# EEZ_DIB_DCM220_r2B6.net
KiCad netlist of a schematic drawn in EAGLE
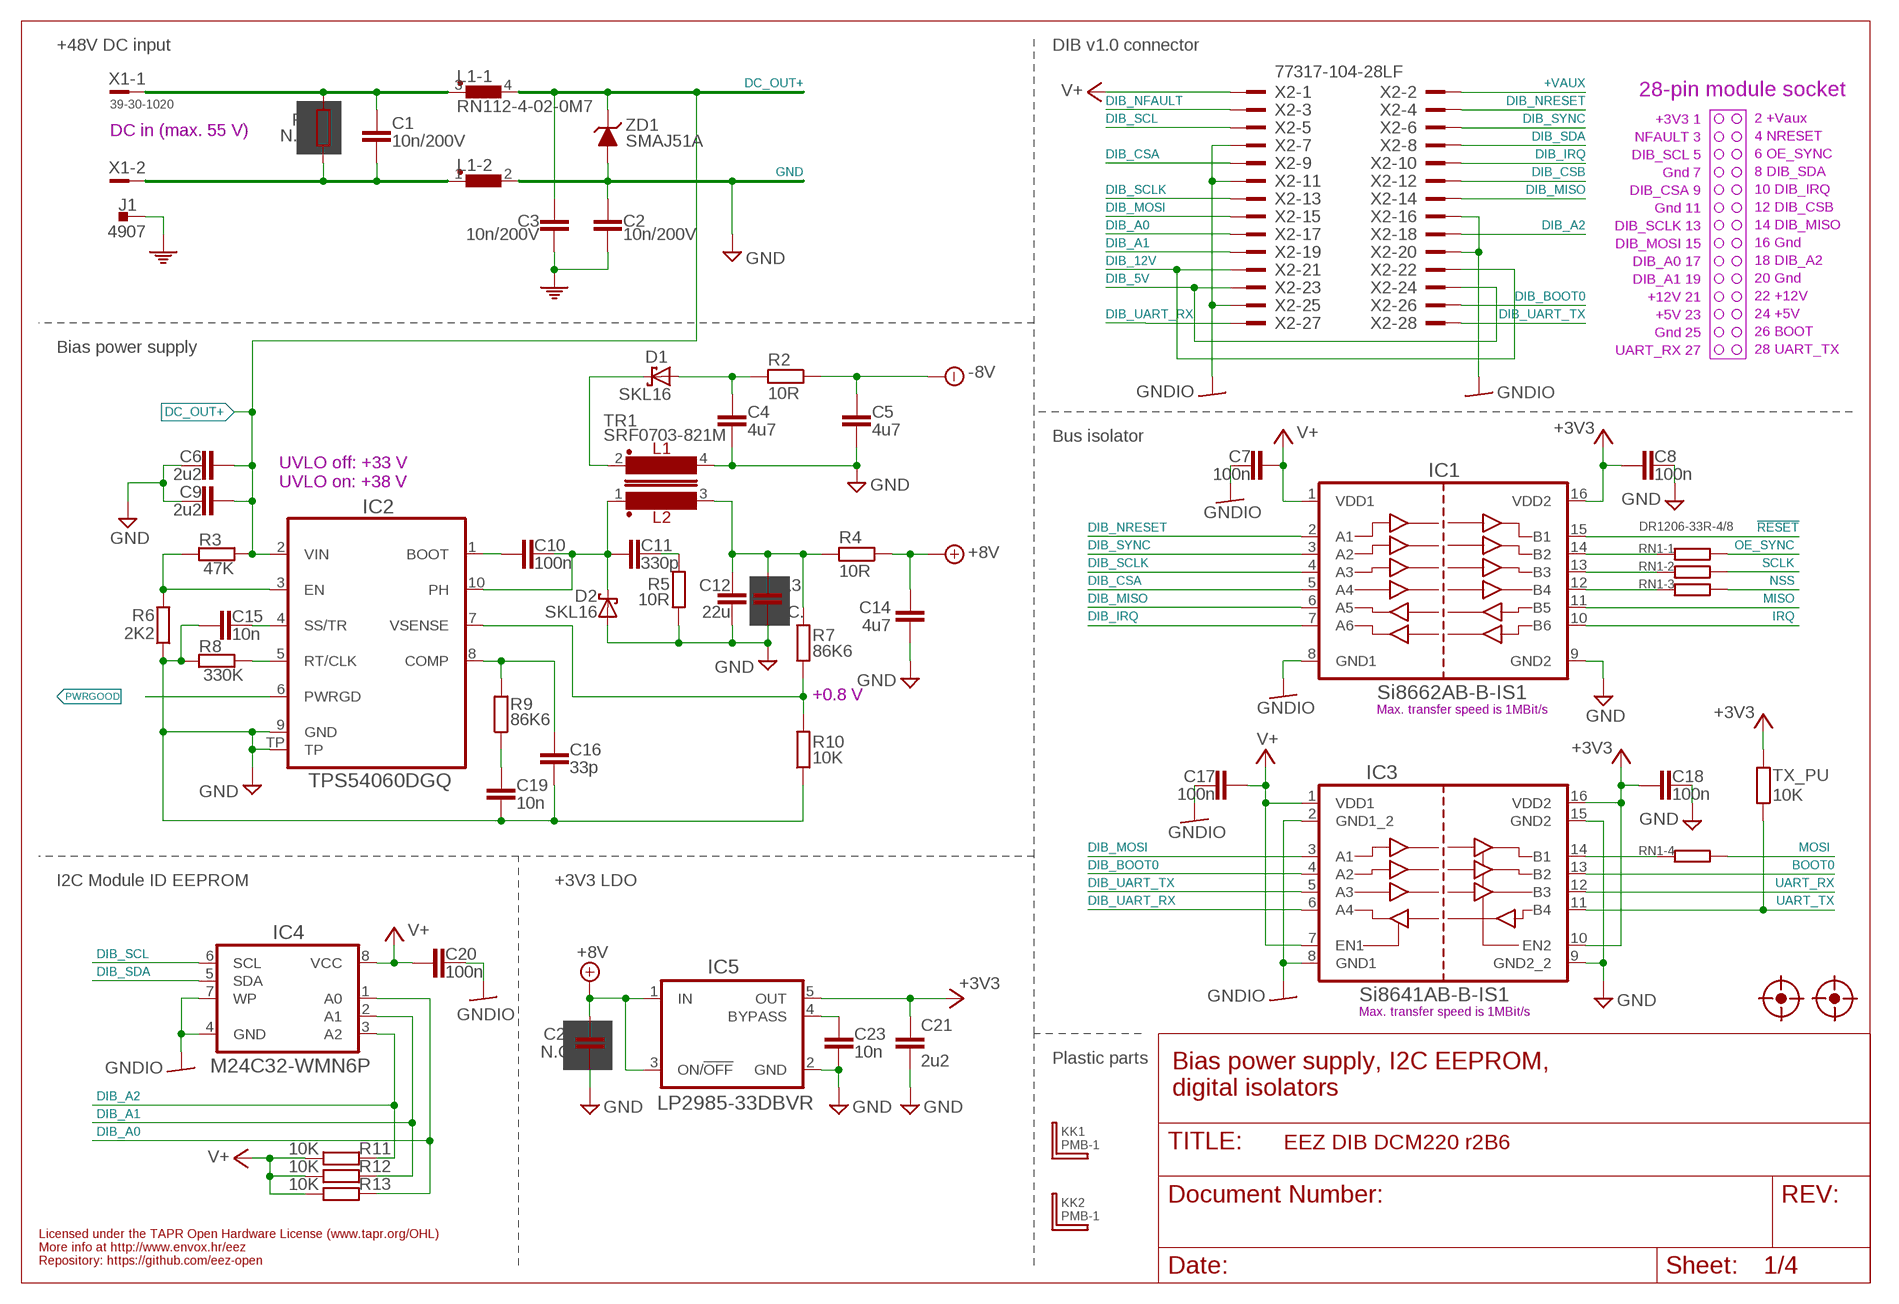
[diagram p0: schematic, sheet 1]
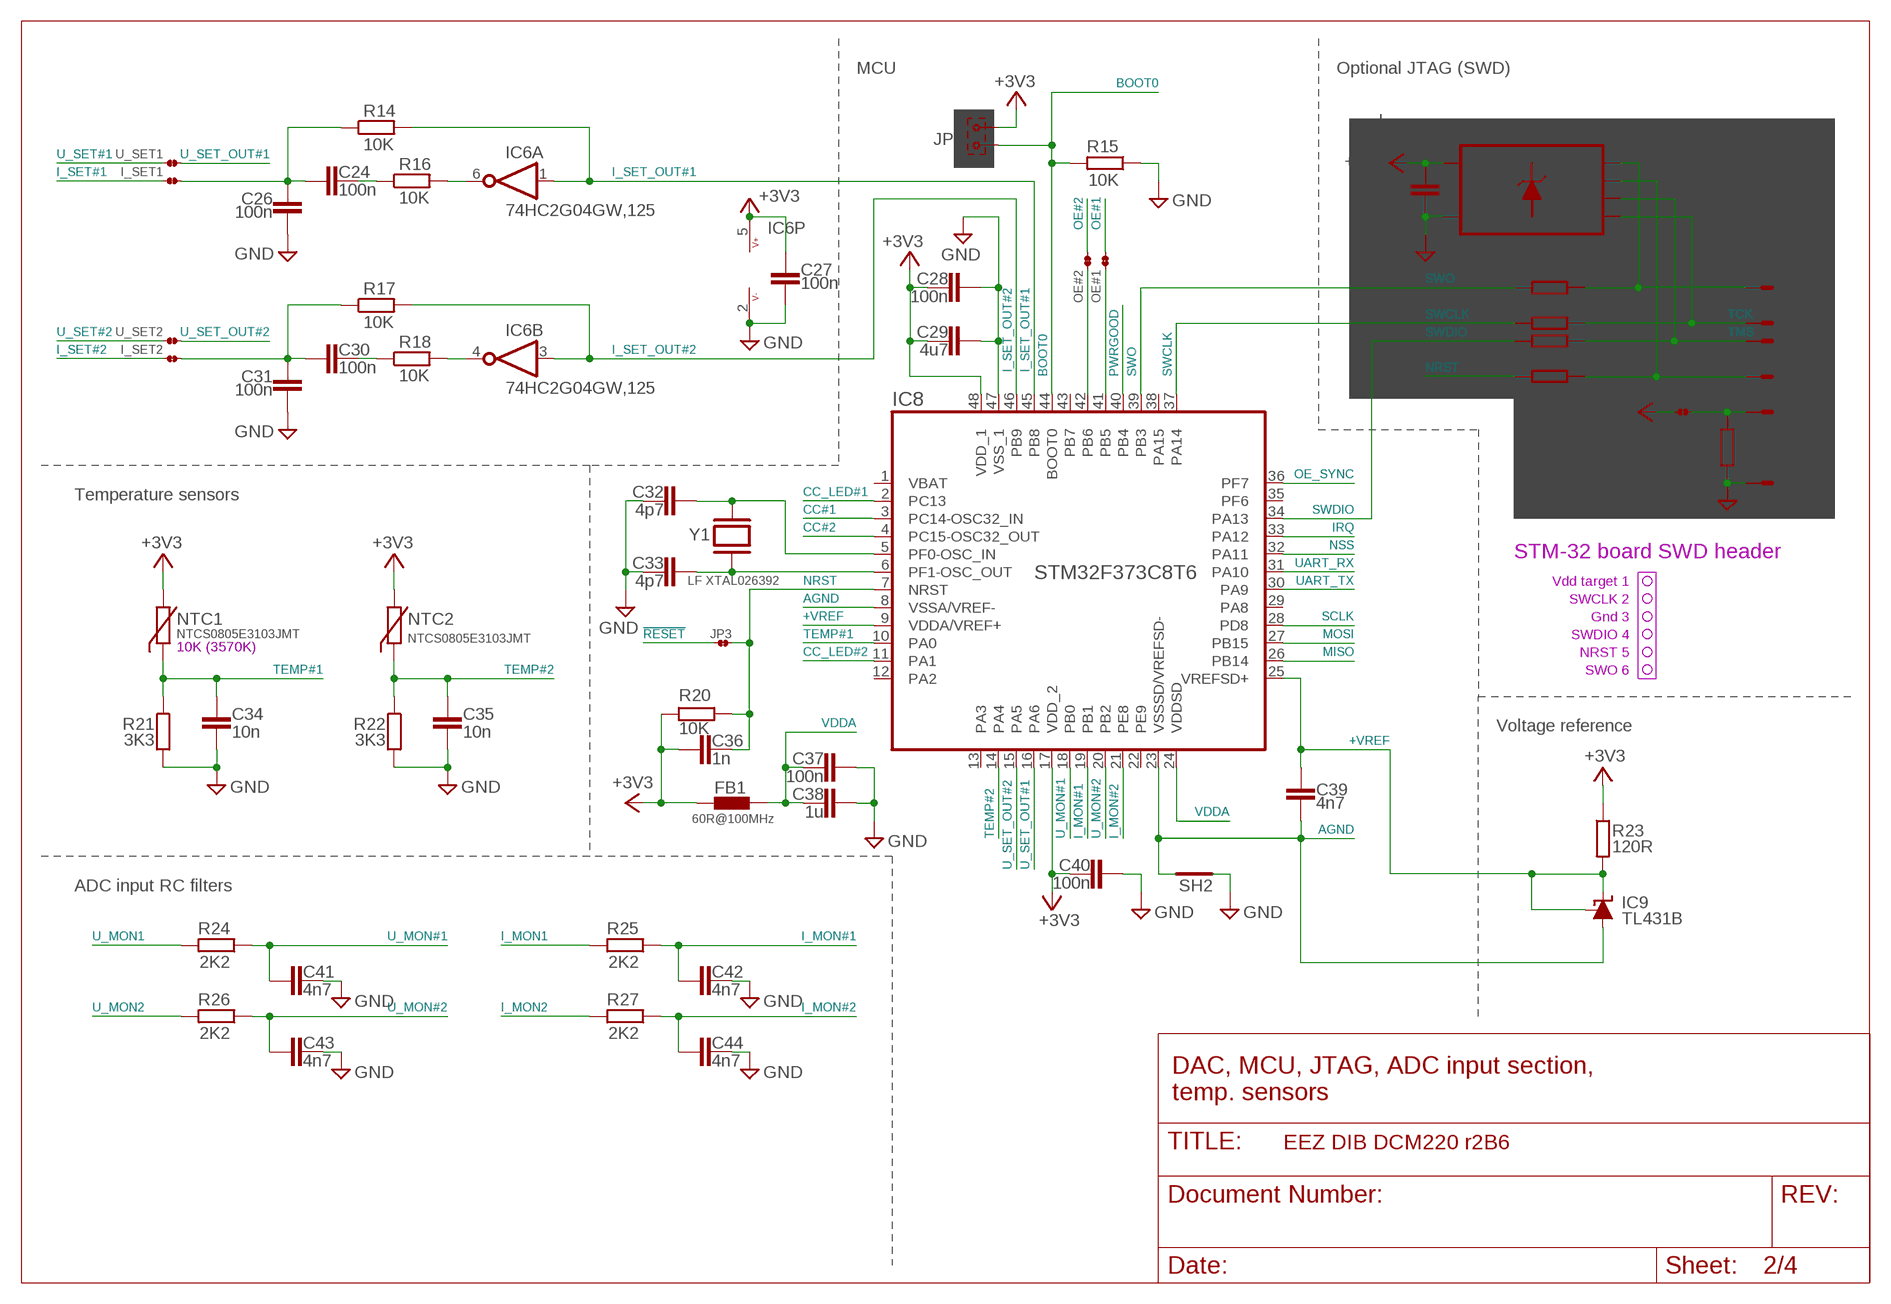
[diagram p1: schematic, sheet 2]
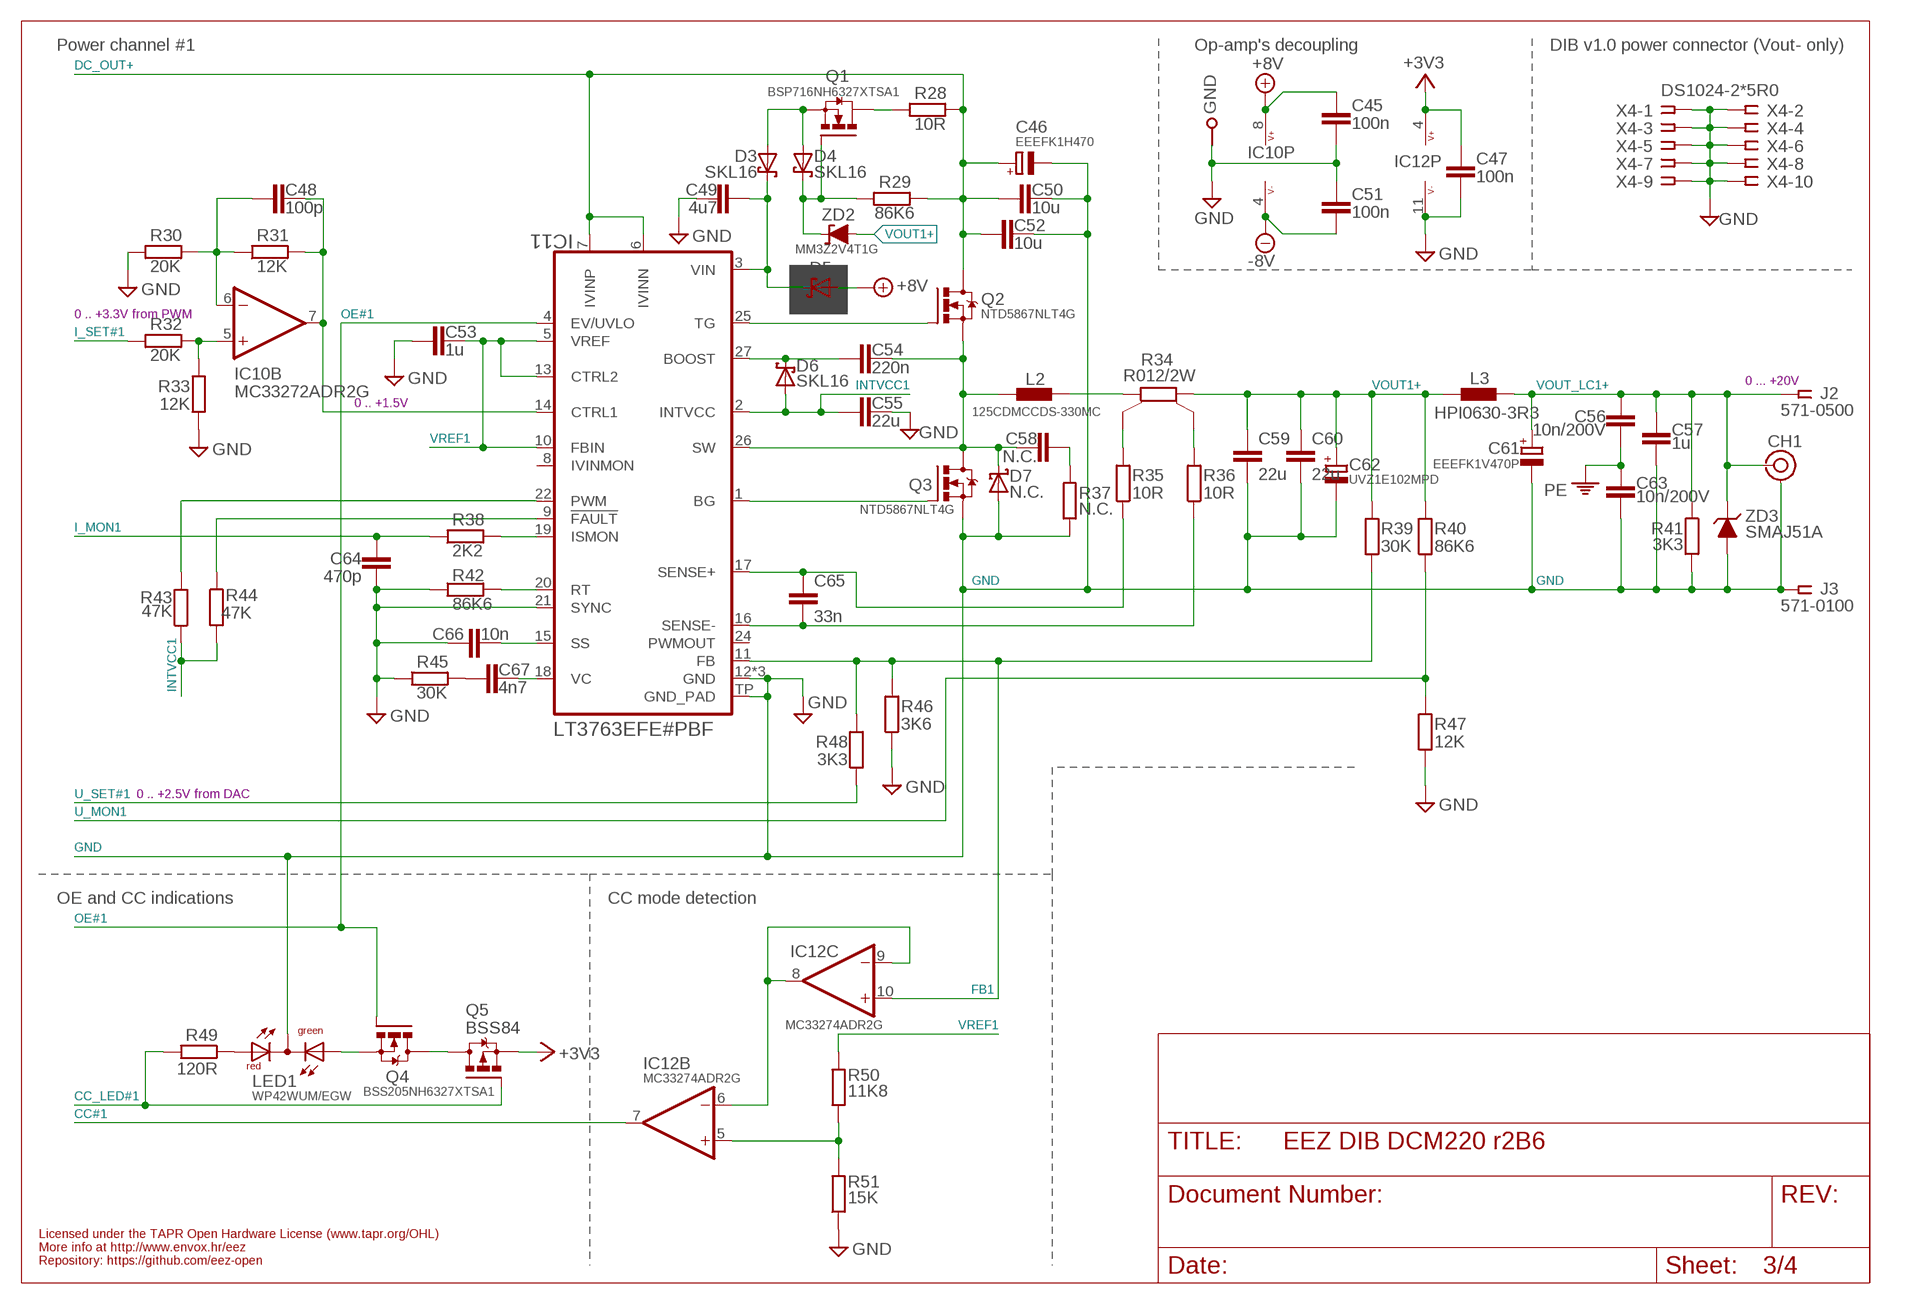
[diagram p2: schematic, sheet 3]
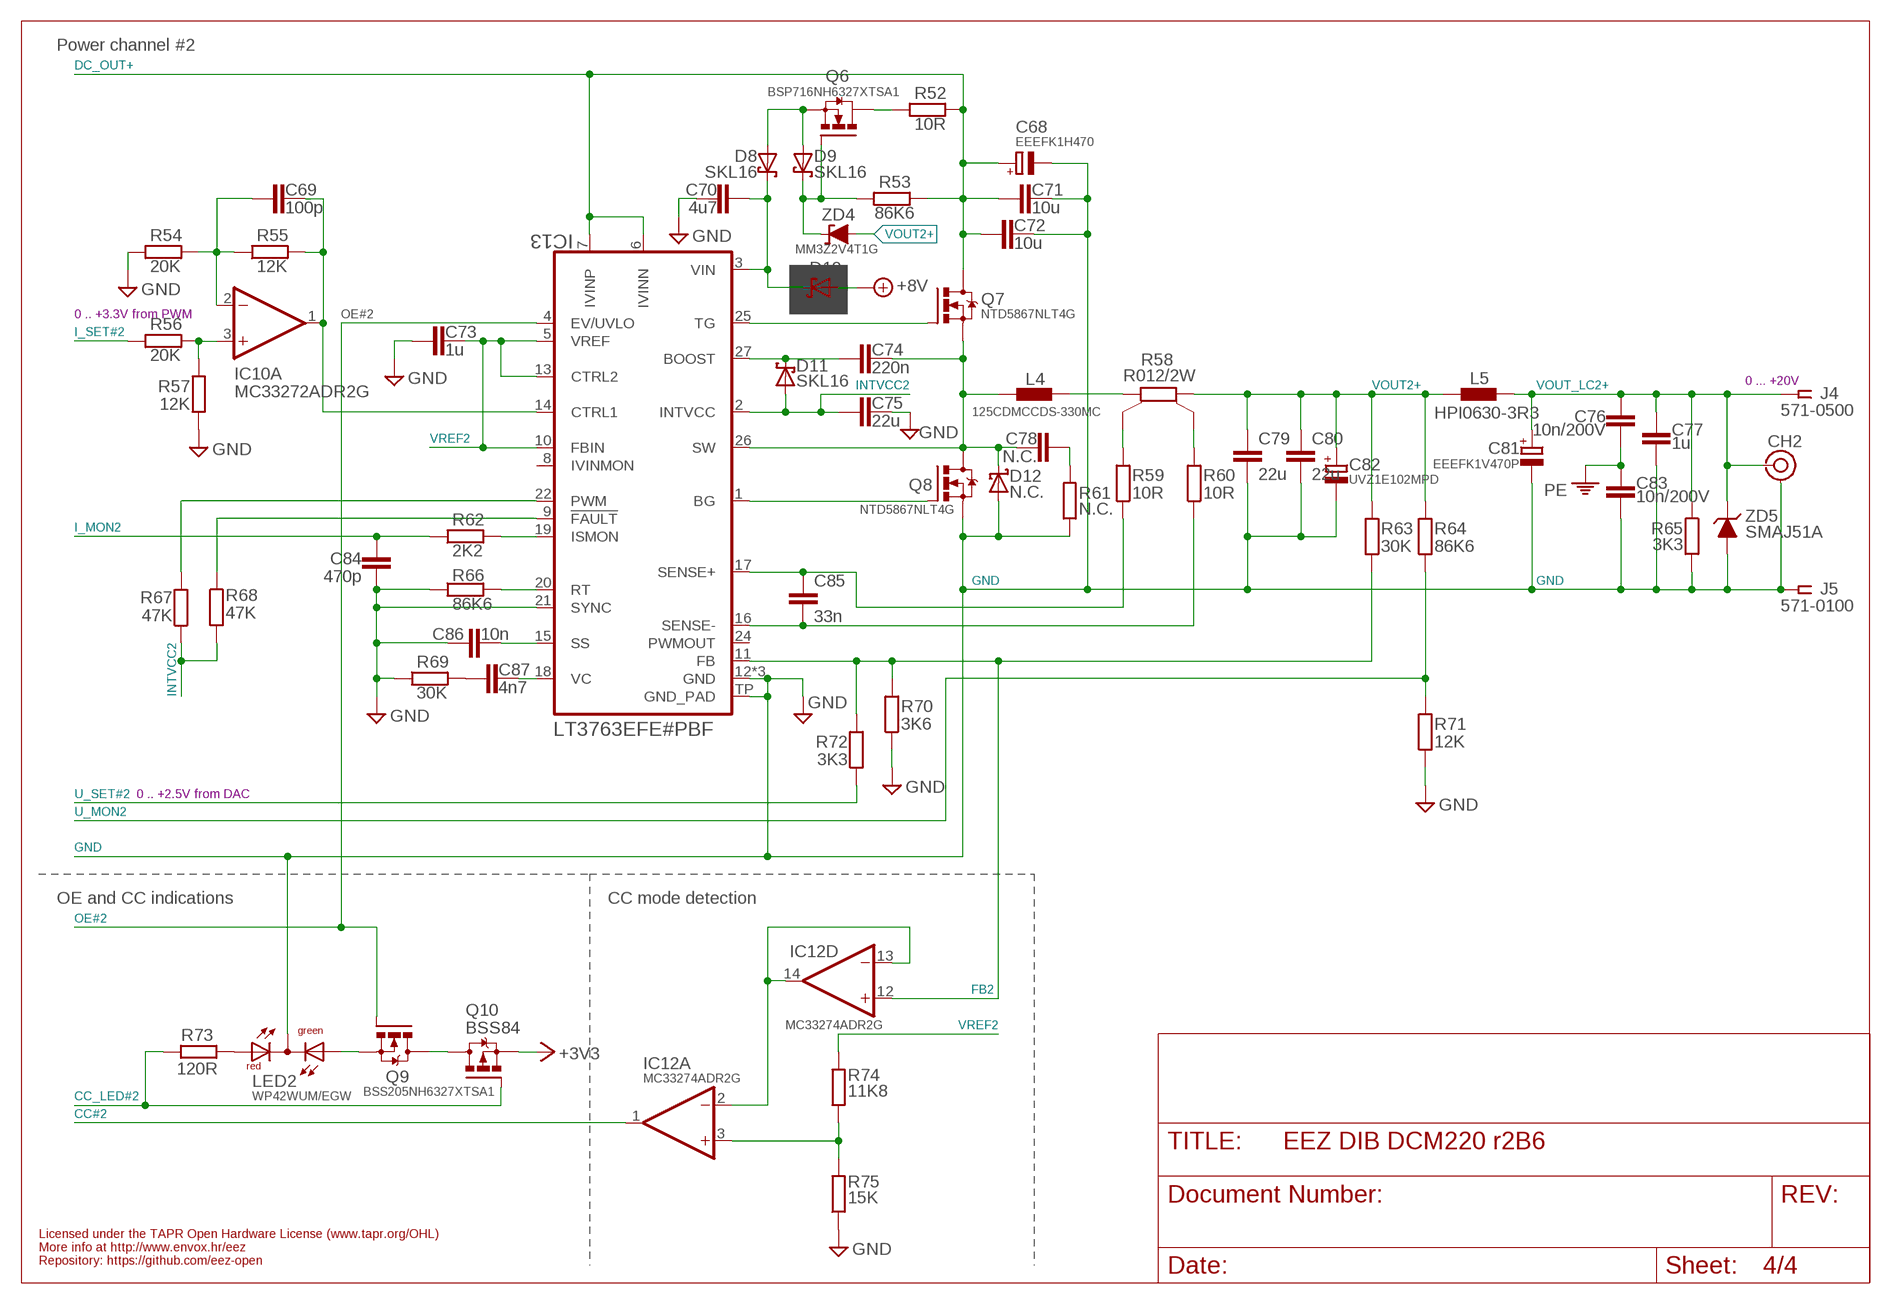
[diagram p3: schematic, sheet 4]

(export (version "E")
  (design (tool "Eeschema 10.0.6"))
  (components
    (comp (ref "C24")
      (value "100n")
      (footprint "eagle-import:C0603")
      (libsource (lib "eagle-import") (part "C-EUC0603"))
    )
    (comp (ref "C25")
      (value "N.C.")
      (footprint "eagle-import:C0603")
      (libsource (lib "eagle-import") (part "C-EUC0603"))
    )
    (comp (ref "C26")
      (value "100n")
      (footprint "eagle-import:C0603")
      (libsource (lib "eagle-import") (part "C-EUC0603"))
    )
    (comp (ref "C27")
      (value "100n")
      (footprint "eagle-import:C0603")
      (libsource (lib "eagle-import") (part "C-EUC0603"))
    )
    (comp (ref "C28")
      (value "100n")
      (footprint "eagle-import:C0603")
      (libsource (lib "eagle-import") (part "C-EUC0603"))
    )
    (comp (ref "C29")
      (value "4u7")
      (footprint "eagle-import:C1206")
      (libsource (lib "eagle-import") (part "C-EUC1206"))
    )
    (comp (ref "C30")
      (value "100n")
      (footprint "eagle-import:C0603")
      (libsource (lib "eagle-import") (part "C-EUC0603"))
    )
    (comp (ref "C31")
      (value "100n")
      (footprint "eagle-import:C0603")
      (libsource (lib "eagle-import") (part "C-EUC0603"))
    )
    (comp (ref "C32")
      (value "4p7")
      (footprint "eagle-import:C0603")
      (libsource (lib "eagle-import") (part "C-EUC0603"))
    )
    (comp (ref "C33")
      (value "4p7")
      (footprint "eagle-import:C0603")
      (libsource (lib "eagle-import") (part "C-EUC0603"))
    )
    (comp (ref "C34")
      (value "10n")
      (footprint "eagle-import:C0805")
      (libsource (lib "eagle-import") (part "C-EUC0805"))
    )
    (comp (ref "C35")
      (value "10n")
      (footprint "eagle-import:C0805")
      (libsource (lib "eagle-import") (part "C-EUC0805"))
    )
    (comp (ref "C36")
      (value "1n")
      (footprint "eagle-import:C0805")
      (libsource (lib "eagle-import") (part "C-EUC0805"))
    )
    (comp (ref "C37")
      (value "100n")
      (footprint "eagle-import:C0603")
      (libsource (lib "eagle-import") (part "C-EUC0603"))
    )
    (comp (ref "C38")
      (value "1u")
      (footprint "eagle-import:C0805")
      (libsource (lib "eagle-import") (part "C-EUC0805"))
    )
    (comp (ref "C39")
      (value "4n7")
      (footprint "eagle-import:C0805")
      (libsource (lib "eagle-import") (part "C-EUC0805"))
    )
    (comp (ref "C40")
      (value "100n")
      (footprint "eagle-import:C0603")
      (libsource (lib "eagle-import") (part "C-EUC0603"))
    )
    (comp (ref "C41")
      (value "4n7")
      (footprint "eagle-import:C0805")
      (libsource (lib "eagle-import") (part "C-EUC0805"))
    )
    (comp (ref "C42")
      (value "4n7")
      (footprint "eagle-import:C0805")
      (libsource (lib "eagle-import") (part "C-EUC0805"))
    )
    (comp (ref "C43")
      (value "4n7")
      (footprint "eagle-import:C0805")
      (libsource (lib "eagle-import") (part "C-EUC0805"))
    )
    (comp (ref "C44")
      (value "4n7")
      (footprint "eagle-import:C0805")
      (libsource (lib "eagle-import") (part "C-EUC0805"))
    )
    (comp (ref "FB1")
      (value "60R@100MHz")
      (footprint "eagle-import:BEAD0603")
      (libsource (lib "eagle-import") (part "FERRITE_BEAD0603"))
    )
    (comp (ref "IC6")
      (value "74HC2G04GW,125")
      (footprint "eagle-import:SOT65P210X110-6N")
      (libsource (lib "eagle-import") (part "74HC2G04"))
    )
    (comp (ref "IC7")
      (value "N.C.")
      (footprint "eagle-import:DRL6")
      (libsource (lib "eagle-import") (part "TPD4E001-DRL"))
    )
    (comp (ref "IC8")
      (value "STM32F373C8T6")
      (footprint "eagle-import:LQFP-48")
      (libsource (lib "eagle-import") (part "STM32F373C8T6"))
    )
    (comp (ref "IC9")
      (value "TL431B")
      (footprint "eagle-import:SOT103P240X110-3N")
      (libsource (lib "eagle-import") (part "TL431"))
    )
    (comp (ref "I_SET1")
      (value "JP2-NOCUT")
      (footprint "eagle-import:JP2-NOCUT")
      (libsource (lib "eagle-import") (part "JP2-NOCUT"))
    )
    (comp (ref "I_SET2")
      (value "JP2-NOCUT")
      (footprint "eagle-import:JP2-NOCUT")
      (libsource (lib "eagle-import") (part "JP2-NOCUT"))
    )
    (comp (ref "JP1")
      (value "JUMPER-2PIN-2MM")
      (footprint "eagle-import:2MM-2")
      (libsource (lib "eagle-import") (part "JUMPER-2PIN-2MM"))
    )
    (comp (ref "JP2")
      (value "JP2-CUT")
      (footprint "eagle-import:JP2-CUT")
      (libsource (lib "eagle-import") (part "JP2-CUT"))
    )
    (comp (ref "JP3")
      (value "JP2-NOCUT")
      (footprint "eagle-import:JP2-NOCUT")
      (libsource (lib "eagle-import") (part "JP2-NOCUT"))
    )
    (comp (ref "NTC1")
      (value "NTCS0805E3103JMT")
      (footprint "eagle-import:R_0805")
      (libsource (lib "eagle-import") (part "NTCR_0805"))
    )
    (comp (ref "NTC2")
      (value "NTCS0805E3103JMT")
      (footprint "eagle-import:R_0805")
      (libsource (lib "eagle-import") (part "NTCR_0805"))
    )
    (comp (ref "OE#1")
      (value "JP2-NOCUT")
      (footprint "eagle-import:JP2-NOCUT")
      (libsource (lib "eagle-import") (part "JP2-NOCUT"))
    )
    (comp (ref "OE#2")
      (value "JP2-NOCUT")
      (footprint "eagle-import:JP2-NOCUT")
      (libsource (lib "eagle-import") (part "JP2-NOCUT"))
    )
    (comp (ref "R14")
      (value "10K")
      (footprint "eagle-import:R0805")
      (libsource (lib "eagle-import") (part "R-EU_R0805"))
    )
    (comp (ref "R15")
      (value "10K")
      (footprint "eagle-import:R0805")
      (libsource (lib "eagle-import") (part "R-EU_R0805"))
    )
    (comp (ref "R16")
      (value "10K")
      (footprint "eagle-import:R0805")
      (libsource (lib "eagle-import") (part "R-EU_R0805"))
    )
    (comp (ref "R17")
      (value "10K")
      (footprint "eagle-import:R0805")
      (libsource (lib "eagle-import") (part "R-EU_R0805"))
    )
    (comp (ref "R18")
      (value "10K")
      (footprint "eagle-import:R0805")
      (libsource (lib "eagle-import") (part "R-EU_R0805"))
    )
    (comp (ref "R19")
      (value "N.C.")
      (footprint "eagle-import:R0805")
      (libsource (lib "eagle-import") (part "R-EU_R0805"))
    )
    (comp (ref "R20")
      (value "10K")
      (footprint "eagle-import:R0805")
      (libsource (lib "eagle-import") (part "R-EU_R0805"))
    )
    (comp (ref "R21")
      (value "3K3")
      (footprint "eagle-import:R0805")
      (libsource (lib "eagle-import") (part "R-EU_R0805"))
    )
    (comp (ref "R22")
      (value "3K3")
      (footprint "eagle-import:R0805")
      (libsource (lib "eagle-import") (part "R-EU_R0805"))
    )
    (comp (ref "R23")
      (value "120R")
      (footprint "eagle-import:R0805")
      (libsource (lib "eagle-import") (part "R-EU_R0805"))
    )
    (comp (ref "R24")
      (value "2K2")
      (footprint "eagle-import:R0805")
      (libsource (lib "eagle-import") (part "R-EU_R0805"))
    )
    (comp (ref "R25")
      (value "2K2")
      (footprint "eagle-import:R0805")
      (libsource (lib "eagle-import") (part "R-EU_R0805"))
    )
    (comp (ref "R26")
      (value "2K2")
      (footprint "eagle-import:R0805")
      (libsource (lib "eagle-import") (part "R-EU_R0805"))
    )
    (comp (ref "R27")
      (value "2K2")
      (footprint "eagle-import:R0805")
      (libsource (lib "eagle-import") (part "R-EU_R0805"))
    )
    (comp (ref "RN2")
      (value "N.C.")
      (footprint "eagle-import:CAY16")
      (libsource (lib "eagle-import") (part "R_ARRAY4"))
    )
    (comp (ref "SH2")
      (value "SHORTNOHOLE")
      (footprint "eagle-import:SHORT_NOHOLE")
      (libsource (lib "eagle-import") (part "SHORTNOHOLE"))
    )
    (comp (ref "U_SET1")
      (value "JP2-NOCUT")
      (footprint "eagle-import:JP2-NOCUT")
      (libsource (lib "eagle-import") (part "JP2-NOCUT"))
    )
    (comp (ref "U_SET2")
      (value "JP2-NOCUT")
      (footprint "eagle-import:JP2-NOCUT")
      (libsource (lib "eagle-import") (part "JP2-NOCUT"))
    )
    (comp (ref "X3")
      (value "N.C.")
      (footprint "eagle-import:22-23-2061")
      (fields (field (name "MF") "MOLEX") (field (name "MPN") "22-23-2061"))
      (libsource (lib "eagle-import") (part "22-23-2061"))
    )
    (comp (ref "Y1")
      (value "LF XTAL026392")
      (footprint "eagle-import:12SMX(B)")
      (libsource (lib "eagle-import") (part "XTAL7.5X5.1-B"))
    )
    (comp (ref "C45")
      (value "100n")
      (footprint "eagle-import:C0603")
      (libsource (lib "eagle-import") (part "C-EUC0603"))
    )
    (comp (ref "C46")
      (value "EEEFK1H470")
      (footprint "eagle-import:CAPAE830X1050N")
      (libsource (lib "eagle-import") (part "ECAPSMD8.3MM/HA0"))
    )
    (comp (ref "C47")
      (value "100n")
      (footprint "eagle-import:C0603")
      (libsource (lib "eagle-import") (part "C-EUC0603"))
    )
    (comp (ref "C48")
      (value "100p")
      (footprint "eagle-import:C0805")
      (libsource (lib "eagle-import") (part "C-EUC0805"))
    )
    (comp (ref "C49")
      (value "4u7")
      (footprint "eagle-import:C1206")
      (libsource (lib "eagle-import") (part "C-EUC1206"))
    )
    (comp (ref "C50")
      (value "10u")
      (footprint "eagle-import:C1210")
      (libsource (lib "eagle-import") (part "C-EUC1210"))
    )
    (comp (ref "C51")
      (value "100n")
      (footprint "eagle-import:C0603")
      (libsource (lib "eagle-import") (part "C-EUC0603"))
    )
    (comp (ref "C52")
      (value "10u")
      (footprint "eagle-import:C1210")
      (libsource (lib "eagle-import") (part "C-EUC1210"))
    )
    (comp (ref "C53")
      (value "1u")
      (footprint "eagle-import:C0805")
      (libsource (lib "eagle-import") (part "C-EUC0805"))
    )
    (comp (ref "C54")
      (value "220n")
      (footprint "eagle-import:C0805")
      (libsource (lib "eagle-import") (part "C-EUC0805"))
    )
    (comp (ref "C55")
      (value "22u")
      (footprint "eagle-import:C1206")
      (libsource (lib "eagle-import") (part "C-EUC1206"))
    )
    (comp (ref "C56")
      (value "10n/200V")
      (footprint "eagle-import:C1206")
      (libsource (lib "eagle-import") (part "C-EUC1206"))
    )
    (comp (ref "C57")
      (value "1u")
      (footprint "eagle-import:C0805")
      (libsource (lib "eagle-import") (part "C-EUC0805"))
    )
    (comp (ref "C58")
      (value "N.C.")
      (footprint "eagle-import:C0805")
      (libsource (lib "eagle-import") (part "C-EUC0805"))
    )
    (comp (ref "C59")
      (value "22u")
      (footprint "eagle-import:C1210")
      (libsource (lib "eagle-import") (part "C-EUC1210"))
    )
    (comp (ref "C60")
      (value "22u")
      (footprint "eagle-import:C1210")
      (libsource (lib "eagle-import") (part "C-EUC1210"))
    )
    (comp (ref "C61")
      (value "EEEFK1V470P")
      (footprint "eagle-import:CAPAE660X610N")
      (libsource (lib "eagle-import") (part "ECAPPANASONIC_H"))
    )
    (comp (ref "C62")
      (value "UVZ1E102MPD")
      (footprint "eagle-import:ECAP5_10.5")
      (libsource (lib "eagle-import") (part "ECAP5G_10.5MM"))
    )
    (comp (ref "C63")
      (value "10n/200V")
      (footprint "eagle-import:C1206")
      (libsource (lib "eagle-import") (part "C-EUC1206"))
    )
    (comp (ref "C64")
      (value "470p")
      (footprint "eagle-import:C0805")
      (libsource (lib "eagle-import") (part "C-EUC0805"))
    )
    (comp (ref "C65")
      (value "33n")
      (footprint "eagle-import:C0805")
      (libsource (lib "eagle-import") (part "C-EUC0805"))
    )
    (comp (ref "C66")
      (value "10n")
      (footprint "eagle-import:C0805")
      (libsource (lib "eagle-import") (part "C-EUC0805"))
    )
    (comp (ref "C67")
      (value "4n7")
      (footprint "eagle-import:C0805")
      (libsource (lib "eagle-import") (part "C-EUC0805"))
    )
    (comp (ref "CH1")
      (value "TEST_POINT-2")
      (footprint "eagle-import:TP_1.1MM_2")
      (libsource (lib "eagle-import") (part "TEST_POINT-2"))
    )
    (comp (ref "D3")
      (value "SKL16")
      (footprint "eagle-import:SOD123")
      (libsource (lib "eagle-import") (part "SCHOTTKYSOD123"))
    )
    (comp (ref "D4")
      (value "SKL16")
      (footprint "eagle-import:SOD123")
      (libsource (lib "eagle-import") (part "SCHOTTKYSOD123"))
    )
    (comp (ref "D5")
      (value "N.C.")
      (footprint "eagle-import:SOD123")
      (libsource (lib "eagle-import") (part "SCHOTTKYSOD123"))
    )
    (comp (ref "D6")
      (value "SKL16")
      (footprint "eagle-import:SOD123")
      (libsource (lib "eagle-import") (part "SCHOTTKYSOD123"))
    )
    (comp (ref "D7")
      (value "N.C.")
      (footprint "eagle-import:SMA")
      (libsource (lib "eagle-import") (part "SCHOTTKYSMA_DO-214AC"))
    )
    (comp (ref "GND")
      (value "TEST-PIN_0.9MM")
      (footprint "eagle-import:TEST-PIN_0.9MM")
      (libsource (lib "eagle-import") (part "TEST-PIN_0.9MM"))
    )
    (comp (ref "IC10")
      (value "MC33272ADR2G")
      (footprint "eagle-import:SOIC127P600X173-8N")
      (libsource (lib "eagle-import") (part "TL072SOIC8"))
    )
    (comp (ref "IC11")
      (value "LT3763EFE#PBF")
      (footprint "eagle-import:LTC_05-08-1663-EB")
      (libsource (lib "eagle-import") (part "LT3763EFE#PBF"))
    )
    (comp (ref "IC12")
      (value "MC33274ADR2G")
      (footprint "eagle-import:SOIC127P600X175-14N")
      (fields (field (name "MPN") "TL074ACD"))
      (libsource (lib "eagle-import") (part "TL074SOIC14"))
    )
    (comp (ref "J2")
      (value "571-0500")
      (footprint "eagle-import:DELTRON_571")
      (libsource (lib "eagle-import") (part "571-0500"))
    )
    (comp (ref "J3")
      (value "571-0100")
      (footprint "eagle-import:DELTRON_571")
      (libsource (lib "eagle-import") (part "571-0100"))
    )
    (comp (ref "L2")
      (value "125CDMCCDS-330MC")
      (footprint "eagle-import:125CDMCC_DS")
      (libsource (lib "eagle-import") (part "125CDMCC/DS"))
    )
    (comp (ref "L3")
      (value "HPI0630-3R3")
      (footprint "eagle-import:COILCRAFT_HPI0630")
      (libsource (lib "eagle-import") (part "COILCRAFT_HPI0630"))
    )
    (comp (ref "LED1")
      (value "WP42WUM/EGW")
      (footprint "eagle-import:L-42WUM-1EGWT")
      (libsource (lib "eagle-import") (part "LED_L-42WUM/1EGWT"))
    )
    (comp (ref "Q1")
      (value "BSP716NH6327XTSA1")
      (footprint "eagle-import:SOT223")
      (libsource (lib "eagle-import") (part "N-HEXFET-2D_?-SOT232IRLL014N"))
    )
    (comp (ref "Q2")
      (value "NTD5867NLT4G")
      (footprint "eagle-import:TO229P990X239-3N")
      (libsource (lib "eagle-import") (part "N-MOSFETDPAK"))
    )
    (comp (ref "Q3")
      (value "NTD5867NLT4G")
      (footprint "eagle-import:TO229P990X239-3N")
      (libsource (lib "eagle-import") (part "N-MOSFETDPAK"))
    )
    (comp (ref "Q4")
      (value "BSS205NH6327XTSA1")
      (footprint "eagle-import:SOT103P240X110-3N")
      (fields (field (name "MPN") "2N7002-7-F"))
      (libsource (lib "eagle-import") (part "2N7002"))
    )
    (comp (ref "Q5")
      (value "BSS84")
      (footprint "eagle-import:SOT95P237X112-3N")
      (fields (field (name "MPN") "IRLML2246TRPBF"))
      (libsource (lib "eagle-import") (part "IRLML2246TRPBF"))
    )
    (comp (ref "R28")
      (value "10R")
      (footprint "eagle-import:R0805")
      (libsource (lib "eagle-import") (part "R-EU_R0805"))
    )
    (comp (ref "R29")
      (value "86K6")
      (footprint "eagle-import:R0805")
      (libsource (lib "eagle-import") (part "R-EU_R0805"))
    )
    (comp (ref "R30")
      (value "20K")
      (footprint "eagle-import:R0805")
      (libsource (lib "eagle-import") (part "R-EU_R0805"))
    )
    (comp (ref "R31")
      (value "12K")
      (footprint "eagle-import:R0805")
      (libsource (lib "eagle-import") (part "R-EU_R0805"))
    )
    (comp (ref "R32")
      (value "20K")
      (footprint "eagle-import:R0805")
      (libsource (lib "eagle-import") (part "R-EU_R0805"))
    )
    (comp (ref "R33")
      (value "12K")
      (footprint "eagle-import:R0805")
      (libsource (lib "eagle-import") (part "R-EU_R0805"))
    )
    (comp (ref "R34")
      (value "R012/2W")
      (footprint "eagle-import:R_2512-4WIRE")
      (libsource (lib "eagle-import") (part "R-EU_4WIRE2512"))
    )
    (comp (ref "R35")
      (value "10R")
      (footprint "eagle-import:R0805")
      (libsource (lib "eagle-import") (part "R-EU_R0805"))
    )
    (comp (ref "R36")
      (value "10R")
      (footprint "eagle-import:R0805")
      (libsource (lib "eagle-import") (part "R-EU_R0805"))
    )
    (comp (ref "R37")
      (value "N.C.")
      (footprint "eagle-import:R1206")
      (libsource (lib "eagle-import") (part "R-EU_R1206"))
    )
    (comp (ref "R38")
      (value "2K2")
      (footprint "eagle-import:R0805")
      (libsource (lib "eagle-import") (part "R-EU_R0805"))
    )
    (comp (ref "R39")
      (value "30K")
      (footprint "eagle-import:R0805")
      (libsource (lib "eagle-import") (part "R-EU_R0805"))
    )
    (comp (ref "R40")
      (value "86K6")
      (footprint "eagle-import:R0805")
      (libsource (lib "eagle-import") (part "R-EU_R0805"))
    )
    (comp (ref "R41")
      (value "3K3")
      (footprint "eagle-import:R0805")
      (libsource (lib "eagle-import") (part "R-EU_R0805"))
    )
    (comp (ref "R42")
      (value "86K6")
      (footprint "eagle-import:R0805")
      (libsource (lib "eagle-import") (part "R-EU_R0805"))
    )
    (comp (ref "R43")
      (value "47K")
      (footprint "eagle-import:R0805")
      (libsource (lib "eagle-import") (part "R-EU_R0805"))
    )
    (comp (ref "R44")
      (value "47K")
      (footprint "eagle-import:R0805")
      (libsource (lib "eagle-import") (part "R-EU_R0805"))
    )
    (comp (ref "R45")
      (value "30K")
      (footprint "eagle-import:R0805")
      (libsource (lib "eagle-import") (part "R-EU_R0805"))
    )
    (comp (ref "R46")
      (value "3K6")
      (footprint "eagle-import:R0805")
      (libsource (lib "eagle-import") (part "R-EU_R0805"))
    )
    (comp (ref "R47")
      (value "12K")
      (footprint "eagle-import:R0805")
      (libsource (lib "eagle-import") (part "R-EU_R0805"))
    )
    (comp (ref "R48")
      (value "3K3")
      (footprint "eagle-import:R0805")
      (libsource (lib "eagle-import") (part "R-EU_R0805"))
    )
    (comp (ref "R49")
      (value "120R")
      (footprint "eagle-import:R0805")
      (libsource (lib "eagle-import") (part "R-EU_R0805"))
    )
    (comp (ref "R50")
      (value "11K8")
      (footprint "eagle-import:R0805")
      (libsource (lib "eagle-import") (part "R-EU_R0805"))
    )
    (comp (ref "R51")
      (value "15K")
      (footprint "eagle-import:R0805")
      (libsource (lib "eagle-import") (part "R-EU_R0805"))
    )
    (comp (ref "X4")
      (value "DS1024-2*5R0")
      (footprint "eagle-import:SSW-105-02-T-D-RA")
      (libsource (lib "eagle-import") (part "SSW-105-02-T-D-RA"))
    )
    (comp (ref "ZD2")
      (value "MM3Z2V4T1G")
      (footprint "eagle-import:SOD323-W")
      (libsource (lib "eagle-import") (part "ZENER-DIODESOD323"))
    )
    (comp (ref "ZD3")
      (value "SMAJ51A")
      (footprint "eagle-import:DO214AA")
      (libsource (lib "eagle-import") (part "P6SMB68A"))
    )
    (comp (ref "C68")
      (value "EEEFK1H470")
      (footprint "eagle-import:CAPAE830X1050N")
      (libsource (lib "eagle-import") (part "ECAPSMD8.3MM/HA0"))
    )
    (comp (ref "C69")
      (value "100p")
      (footprint "eagle-import:C0805")
      (libsource (lib "eagle-import") (part "C-EUC0805"))
    )
    (comp (ref "C70")
      (value "4u7")
      (footprint "eagle-import:C1206")
      (libsource (lib "eagle-import") (part "C-EUC1206"))
    )
    (comp (ref "C71")
      (value "10u")
      (footprint "eagle-import:C1210")
      (libsource (lib "eagle-import") (part "C-EUC1210"))
    )
    (comp (ref "C72")
      (value "10u")
      (footprint "eagle-import:C1210")
      (libsource (lib "eagle-import") (part "C-EUC1210"))
    )
    (comp (ref "C73")
      (value "1u")
      (footprint "eagle-import:C0805")
      (libsource (lib "eagle-import") (part "C-EUC0805"))
    )
    (comp (ref "C74")
      (value "220n")
      (footprint "eagle-import:C0805")
      (libsource (lib "eagle-import") (part "C-EUC0805"))
    )
    (comp (ref "C75")
      (value "22u")
      (footprint "eagle-import:C1206")
      (libsource (lib "eagle-import") (part "C-EUC1206"))
    )
    (comp (ref "C76")
      (value "10n/200V")
      (footprint "eagle-import:C1206")
      (libsource (lib "eagle-import") (part "C-EUC1206"))
    )
    (comp (ref "C77")
      (value "1u")
      (footprint "eagle-import:C0805")
      (libsource (lib "eagle-import") (part "C-EUC0805"))
    )
    (comp (ref "C78")
      (value "N.C.")
      (footprint "eagle-import:C0805")
      (libsource (lib "eagle-import") (part "C-EUC0805"))
    )
    (comp (ref "C79")
      (value "22u")
      (footprint "eagle-import:C1210")
      (libsource (lib "eagle-import") (part "C-EUC1210"))
    )
    (comp (ref "C80")
      (value "22u")
      (footprint "eagle-import:C1210")
      (libsource (lib "eagle-import") (part "C-EUC1210"))
    )
    (comp (ref "C81")
      (value "EEEFK1V470P")
      (footprint "eagle-import:CAPAE660X610N")
      (libsource (lib "eagle-import") (part "ECAPPANASONIC_H"))
    )
    (comp (ref "C82")
      (value "UVZ1E102MPD")
      (footprint "eagle-import:ECAP5_10.5")
      (libsource (lib "eagle-import") (part "ECAP5G_10.5MM"))
    )
    (comp (ref "C83")
      (value "10n/200V")
      (footprint "eagle-import:C1206")
      (libsource (lib "eagle-import") (part "C-EUC1206"))
    )
    (comp (ref "C84")
      (value "470p")
      (footprint "eagle-import:C0805")
      (libsource (lib "eagle-import") (part "C-EUC0805"))
    )
    (comp (ref "C85")
      (value "33n")
      (footprint "eagle-import:C0805")
      (libsource (lib "eagle-import") (part "C-EUC0805"))
    )
    (comp (ref "C86")
      (value "10n")
      (footprint "eagle-import:C0805")
      (libsource (lib "eagle-import") (part "C-EUC0805"))
    )
    (comp (ref "C87")
      (value "4n7")
      (footprint "eagle-import:C0805")
      (libsource (lib "eagle-import") (part "C-EUC0805"))
    )
    (comp (ref "CH2")
      (value "TEST_POINT-2")
      (footprint "eagle-import:TP_1.1MM_2")
      (libsource (lib "eagle-import") (part "TEST_POINT-2"))
    )
    (comp (ref "D8")
      (value "SKL16")
      (footprint "eagle-import:SOD123")
      (libsource (lib "eagle-import") (part "SCHOTTKYSOD123"))
    )
    (comp (ref "D9")
      (value "SKL16")
      (footprint "eagle-import:SOD123")
      (libsource (lib "eagle-import") (part "SCHOTTKYSOD123"))
    )
    (comp (ref "D10")
      (value "N.C.")
      (footprint "eagle-import:SOD123")
      (libsource (lib "eagle-import") (part "SCHOTTKYSOD123"))
    )
    (comp (ref "D11")
      (value "SKL16")
      (footprint "eagle-import:SOD123")
      (libsource (lib "eagle-import") (part "SCHOTTKYSOD123"))
    )
    (comp (ref "D12")
      (value "N.C.")
      (footprint "eagle-import:SMA")
      (libsource (lib "eagle-import") (part "SCHOTTKYSMA_DO-214AC"))
    )
    (comp (ref "IC13")
      (value "LT3763EFE#PBF")
      (footprint "eagle-import:LTC_05-08-1663-EB")
      (libsource (lib "eagle-import") (part "LT3763EFE#PBF"))
    )
    (comp (ref "J4")
      (value "571-0500")
      (footprint "eagle-import:DELTRON_571")
      (libsource (lib "eagle-import") (part "571-0500"))
    )
    (comp (ref "J5")
      (value "571-0100")
      (footprint "eagle-import:DELTRON_571")
      (libsource (lib "eagle-import") (part "571-0100"))
    )
    (comp (ref "L4")
      (value "125CDMCCDS-330MC")
      (footprint "eagle-import:125CDMCC_DS")
      (libsource (lib "eagle-import") (part "125CDMCC/DS"))
    )
    (comp (ref "L5")
      (value "HPI0630-3R3")
      (footprint "eagle-import:COILCRAFT_HPI0630")
      (libsource (lib "eagle-import") (part "COILCRAFT_HPI0630"))
    )
    (comp (ref "LED2")
      (value "WP42WUM/EGW")
      (footprint "eagle-import:L-42WUM-1EGWT")
      (libsource (lib "eagle-import") (part "LED_L-42WUM/1EGWT"))
    )
    (comp (ref "Q6")
      (value "BSP716NH6327XTSA1")
      (footprint "eagle-import:SOT223")
      (libsource (lib "eagle-import") (part "N-HEXFET-2D_?-SOT232IRLL014N"))
    )
    (comp (ref "Q7")
      (value "NTD5867NLT4G")
      (footprint "eagle-import:TO229P990X239-3N")
      (libsource (lib "eagle-import") (part "N-MOSFETDPAK"))
    )
    (comp (ref "Q8")
      (value "NTD5867NLT4G")
      (footprint "eagle-import:TO229P990X239-3N")
      (libsource (lib "eagle-import") (part "N-MOSFETDPAK"))
    )
    (comp (ref "Q9")
      (value "BSS205NH6327XTSA1")
      (footprint "eagle-import:SOT103P240X110-3N")
      (fields (field (name "MPN") "2N7002-7-F"))
      (libsource (lib "eagle-import") (part "2N7002"))
    )
    (comp (ref "Q10")
      (value "BSS84")
      (footprint "eagle-import:SOT95P237X112-3N")
      (fields (field (name "MPN") "IRLML2246TRPBF"))
      (libsource (lib "eagle-import") (part "IRLML2246TRPBF"))
    )
    (comp (ref "R52")
      (value "10R")
      (footprint "eagle-import:R0805")
      (libsource (lib "eagle-import") (part "R-EU_R0805"))
    )
    (comp (ref "R53")
      (value "86K6")
      (footprint "eagle-import:R0805")
      (libsource (lib "eagle-import") (part "R-EU_R0805"))
    )
    (comp (ref "R54")
      (value "20K")
      (footprint "eagle-import:R0805")
      (libsource (lib "eagle-import") (part "R-EU_R0805"))
    )
    (comp (ref "R55")
      (value "12K")
      (footprint "eagle-import:R0805")
      (libsource (lib "eagle-import") (part "R-EU_R0805"))
    )
    (comp (ref "R56")
      (value "20K")
      (footprint "eagle-import:R0805")
      (libsource (lib "eagle-import") (part "R-EU_R0805"))
    )
    (comp (ref "R57")
      (value "12K")
      (footprint "eagle-import:R0805")
      (libsource (lib "eagle-import") (part "R-EU_R0805"))
    )
    (comp (ref "R58")
      (value "R012/2W")
      (footprint "eagle-import:R_2512-4WIRE")
      (libsource (lib "eagle-import") (part "R-EU_4WIRE2512"))
    )
    (comp (ref "R59")
      (value "10R")
      (footprint "eagle-import:R0805")
      (libsource (lib "eagle-import") (part "R-EU_R0805"))
    )
    (comp (ref "R60")
      (value "10R")
      (footprint "eagle-import:R0805")
      (libsource (lib "eagle-import") (part "R-EU_R0805"))
    )
    (comp (ref "R61")
      (value "N.C.")
      (footprint "eagle-import:R1206")
      (libsource (lib "eagle-import") (part "R-EU_R1206"))
    )
    (comp (ref "R62")
      (value "2K2")
      (footprint "eagle-import:R0805")
      (libsource (lib "eagle-import") (part "R-EU_R0805"))
    )
    (comp (ref "R63")
      (value "30K")
      (footprint "eagle-import:R0805")
      (libsource (lib "eagle-import") (part "R-EU_R0805"))
    )
    (comp (ref "R64")
      (value "86K6")
      (footprint "eagle-import:R0805")
      (libsource (lib "eagle-import") (part "R-EU_R0805"))
    )
    (comp (ref "R65")
      (value "3K3")
      (footprint "eagle-import:R0805")
      (libsource (lib "eagle-import") (part "R-EU_R0805"))
    )
    (comp (ref "R66")
      (value "86K6")
      (footprint "eagle-import:R0805")
      (libsource (lib "eagle-import") (part "R-EU_R0805"))
    )
    (comp (ref "R67")
      (value "47K")
      (footprint "eagle-import:R0805")
      (libsource (lib "eagle-import") (part "R-EU_R0805"))
    )
    (comp (ref "R68")
      (value "47K")
      (footprint "eagle-import:R0805")
      (libsource (lib "eagle-import") (part "R-EU_R0805"))
    )
    (comp (ref "R69")
      (value "30K")
      (footprint "eagle-import:R0805")
      (libsource (lib "eagle-import") (part "R-EU_R0805"))
    )
    (comp (ref "R70")
      (value "3K6")
      (footprint "eagle-import:R0805")
      (libsource (lib "eagle-import") (part "R-EU_R0805"))
    )
    (comp (ref "R71")
      (value "12K")
      (footprint "eagle-import:R0805")
      (libsource (lib "eagle-import") (part "R-EU_R0805"))
    )
    (comp (ref "R72")
      (value "3K3")
      (footprint "eagle-import:R0805")
      (libsource (lib "eagle-import") (part "R-EU_R0805"))
    )
    (comp (ref "R73")
      (value "120R")
      (footprint "eagle-import:R0805")
      (libsource (lib "eagle-import") (part "R-EU_R0805"))
    )
    (comp (ref "R74")
      (value "11K8")
      (footprint "eagle-import:R0805")
      (libsource (lib "eagle-import") (part "R-EU_R0805"))
    )
    (comp (ref "R75")
      (value "15K")
      (footprint "eagle-import:R0805")
      (libsource (lib "eagle-import") (part "R-EU_R0805"))
    )
    (comp (ref "ZD4")
      (value "MM3Z2V4T1G")
      (footprint "eagle-import:SOD323-W")
      (libsource (lib "eagle-import") (part "ZENER-DIODESOD323"))
    )
    (comp (ref "ZD5")
      (value "SMAJ51A")
      (footprint "eagle-import:DO214AA")
      (libsource (lib "eagle-import") (part "P6SMB68A"))
    )
    (comp (ref "C1")
      (value "10n/200V")
      (footprint "eagle-import:C1206")
      (libsource (lib "eagle-import") (part "C-EUC1206"))
    )
    (comp (ref "C2")
      (value "10n/200V")
      (footprint "eagle-import:C1206")
      (libsource (lib "eagle-import") (part "C-EUC1206"))
    )
    (comp (ref "C3")
      (value "10n/200V")
      (footprint "eagle-import:C1206")
      (libsource (lib "eagle-import") (part "C-EUC1206"))
    )
    (comp (ref "C4")
      (value "4u7")
      (footprint "eagle-import:C1206")
      (libsource (lib "eagle-import") (part "C-EUC1206"))
    )
    (comp (ref "C5")
      (value "4u7")
      (footprint "eagle-import:C1206")
      (libsource (lib "eagle-import") (part "C-EUC1206"))
    )
    (comp (ref "C6")
      (value "2u2")
      (footprint "eagle-import:C1206")
      (libsource (lib "eagle-import") (part "C-EUC1206"))
    )
    (comp (ref "C7")
      (value "100n")
      (footprint "eagle-import:C0603")
      (libsource (lib "eagle-import") (part "C-EUC0603"))
    )
    (comp (ref "C8")
      (value "100n")
      (footprint "eagle-import:C0603")
      (libsource (lib "eagle-import") (part "C-EUC0603"))
    )
    (comp (ref "C9")
      (value "2u2")
      (footprint "eagle-import:C1206")
      (libsource (lib "eagle-import") (part "C-EUC1206"))
    )
    (comp (ref "C10")
      (value "100n")
      (footprint "eagle-import:C0603")
      (libsource (lib "eagle-import") (part "C-EUC0603"))
    )
    (comp (ref "C11")
      (value "330p")
      (footprint "eagle-import:C0805")
      (libsource (lib "eagle-import") (part "C-EUC0805"))
    )
    (comp (ref "C12")
      (value "22u")
      (footprint "eagle-import:C1206")
      (libsource (lib "eagle-import") (part "C-EUC1206"))
    )
    (comp (ref "C13")
      (value "N.C.")
      (footprint "eagle-import:C1206")
      (libsource (lib "eagle-import") (part "C-EUC1206"))
    )
    (comp (ref "C14")
      (value "4u7")
      (footprint "eagle-import:C1206")
      (libsource (lib "eagle-import") (part "C-EUC1206"))
    )
    (comp (ref "C15")
      (value "10n")
      (footprint "eagle-import:C0805")
      (libsource (lib "eagle-import") (part "C-EUC0805"))
    )
    (comp (ref "C16")
      (value "33p")
      (footprint "eagle-import:C0603")
      (libsource (lib "eagle-import") (part "C-EUC0603"))
    )
    (comp (ref "C17")
      (value "100n")
      (footprint "eagle-import:C0603")
      (libsource (lib "eagle-import") (part "C-EUC0603"))
    )
    (comp (ref "C18")
      (value "100n")
      (footprint "eagle-import:C0603")
      (libsource (lib "eagle-import") (part "C-EUC0603"))
    )
    (comp (ref "C19")
      (value "10n")
      (footprint "eagle-import:C0805")
      (libsource (lib "eagle-import") (part "C-EUC0805"))
    )
    (comp (ref "C20")
      (value "100n")
      (footprint "eagle-import:C0603")
      (libsource (lib "eagle-import") (part "C-EUC0603"))
    )
    (comp (ref "C21")
      (value "2u2")
      (footprint "eagle-import:C1206")
      (libsource (lib "eagle-import") (part "C-EUC1206"))
    )
    (comp (ref "C22")
      (value "N.C.")
      (footprint "eagle-import:C0805")
      (libsource (lib "eagle-import") (part "C-EUC0805"))
    )
    (comp (ref "C23")
      (value "10n")
      (footprint "eagle-import:C0805")
      (libsource (lib "eagle-import") (part "C-EUC0805"))
    )
    (comp (ref "D1")
      (value "SKL16")
      (footprint "eagle-import:SOD123")
      (libsource (lib "eagle-import") (part "SCHOTTKYSOD123"))
    )
    (comp (ref "D2")
      (value "SKL16")
      (footprint "eagle-import:SOD123")
      (libsource (lib "eagle-import") (part "SCHOTTKYSOD123"))
    )
    (comp (ref "FM1")
      (value "FIDUCIAL_2")
      (footprint "eagle-import:FIDUCIAL_DUAL")
      (libsource (lib "eagle-import") (part "FIDUCIAL_2"))
    )
    (comp (ref "FM2")
      (value "FIDUCIAL_2")
      (footprint "eagle-import:FIDUCIAL_DUAL")
      (libsource (lib "eagle-import") (part "FIDUCIAL_2"))
    )
    (comp (ref "IC1")
      (value "Si8662AB-B-IS1")
      (footprint "eagle-import:SOIC-16")
      (libsource (lib "eagle-import") (part "SI8662NSOIC-16"))
    )
    (comp (ref "IC2")
      (value "TPS54060DGQ")
      (footprint "eagle-import:SOP50P490X110-11N")
      (fields (field (name "MPN") "TPS54060ADGQ"))
      (libsource (lib "eagle-import") (part "TPS54060DGQ"))
    )
    (comp (ref "IC3")
      (value "Si8641AB-B-IS1")
      (footprint "eagle-import:SOIC-16")
      (libsource (lib "eagle-import") (part "SI8641NSOIC-16"))
    )
    (comp (ref "IC4")
      (value "M24C32-WMN6P")
      (footprint "eagle-import:SOIC127P600X173-8N")
      (libsource (lib "eagle-import") (part "AT24CXXSOIC8"))
    )
    (comp (ref "IC5")
      (value "LP2985-33DBVR")
      (footprint "eagle-import:SOT95P270X145-5N")
      (libsource (lib "eagle-import") (part "LP2985"))
    )
    (comp (ref "J1")
      (value "4907")
      (footprint "eagle-import:PCB_TAB-4907")
      (libsource (lib "eagle-import") (part "PCB_TAB-4907"))
    )
    (comp (ref "KK1")
      (value "PMB-1")
      (footprint "eagle-import:PCB-MB")
      (libsource (lib "eagle-import") (part "PCB-MB"))
    )
    (comp (ref "KK2")
      (value "PMB-1")
      (footprint "eagle-import:PCB-MB")
      (libsource (lib "eagle-import") (part "PCB-MB"))
    )
    (comp (ref "L1")
      (value "RN112-4-02-0M7")
      (footprint "eagle-import:RN112")
      (libsource (lib "eagle-import") (part "RN112"))
    )
    (comp (ref "R1")
      (value "N.C.")
      (footprint "eagle-import:R2512")
      (libsource (lib "eagle-import") (part "R-EU_R2512"))
    )
    (comp (ref "R2")
      (value "10R")
      (footprint "eagle-import:R0805")
      (libsource (lib "eagle-import") (part "R-EU_R0805"))
    )
    (comp (ref "R3")
      (value "47K")
      (footprint "eagle-import:R0805")
      (libsource (lib "eagle-import") (part "R-EU_R0805"))
    )
    (comp (ref "R4")
      (value "10R")
      (footprint "eagle-import:R0805")
      (libsource (lib "eagle-import") (part "R-EU_R0805"))
    )
    (comp (ref "R5")
      (value "10R")
      (footprint "eagle-import:R0805")
      (libsource (lib "eagle-import") (part "R-EU_R0805"))
    )
    (comp (ref "R6")
      (value "2K2")
      (footprint "eagle-import:R0805")
      (libsource (lib "eagle-import") (part "R-EU_R0805"))
    )
    (comp (ref "R7")
      (value "86K6")
      (footprint "eagle-import:R0805")
      (libsource (lib "eagle-import") (part "R-EU_R0805"))
    )
    (comp (ref "R8")
      (value "330K")
      (footprint "eagle-import:R0805")
      (libsource (lib "eagle-import") (part "R-EU_R0805"))
    )
    (comp (ref "R9")
      (value "86K6")
      (footprint "eagle-import:R0805")
      (libsource (lib "eagle-import") (part "R-EU_R0805"))
    )
    (comp (ref "R10")
      (value "10K")
      (footprint "eagle-import:R0805")
      (libsource (lib "eagle-import") (part "R-EU_R0805"))
    )
    (comp (ref "R11")
      (value "10K")
      (footprint "eagle-import:R0805")
      (libsource (lib "eagle-import") (part "R-EU_R0805"))
    )
    (comp (ref "R12")
      (value "10K")
      (footprint "eagle-import:R0805")
      (libsource (lib "eagle-import") (part "R-EU_R0805"))
    )
    (comp (ref "R13")
      (value "10K")
      (footprint "eagle-import:R0805")
      (libsource (lib "eagle-import") (part "R-EU_R0805"))
    )
    (comp (ref "RN1")
      (value "DR1206-33R-4/8")
      (footprint "eagle-import:CAY16")
      (libsource (lib "eagle-import") (part "R_ARRAY4"))
    )
    (comp (ref "TR1")
      (value "SRF0703-821M")
      (footprint "eagle-import:SRF0703")
      (libsource (lib "eagle-import") (part "BOURNS_SRF0703INV"))
    )
    (comp (ref "TX_PU")
      (value "10K")
      (footprint "eagle-import:R0805")
      (libsource (lib "eagle-import") (part "R-EU_R0805"))
    )
    (comp (ref "X1")
      (value "39-30-1020")
      (footprint "eagle-import:MINIFIT_39301020")
      (libsource (lib "eagle-import") (part "MINIFIT_39301020"))
    )
    (comp (ref "X2")
      (value "77317-104-28LF")
      (footprint "eagle-import:77317-104-28LF")
      (libsource (lib "eagle-import") (part "77317-104-28LF"))
    )
    (comp (ref "ZD1")
      (value "SMAJ51A")
      (footprint "eagle-import:DO214AA")
      (libsource (lib "eagle-import") (part "P6SMB68A"))
    )
  )
  (nets
    (net (code "1") (name "+3V3") (class "Default")
      (node (ref "C18") (pin "2") (pinfunction "2_2") (pintype "passive"))
      (node (ref "C21") (pin "1") (pinfunction "1_1") (pintype "passive"))
      (node (ref "C25") (pin "1") (pinfunction "1_1") (pintype "passive"))
      (node (ref "C27") (pin "1") (pinfunction "1_1") (pintype "passive"))
      (node (ref "C28") (pin "2") (pinfunction "2_2") (pintype "passive"))
      (node (ref "C29") (pin "1") (pinfunction "1_1") (pintype "passive"))
      (node (ref "C36") (pin "2") (pinfunction "2_2") (pintype "passive"))
      (node (ref "C40") (pin "2") (pinfunction "2_2") (pintype "passive"))
      (node (ref "C47") (pin "1") (pinfunction "1_1") (pintype "passive"))
      (node (ref "C8") (pin "2") (pinfunction "2_2") (pintype "passive"))
      (node (ref "FB1") (pin "P$1") (pinfunction "1_P$1") (pintype "passive"))
      (node (ref "IC1") (pin "16") (pinfunction "VDD2_16") (pintype "passive"))
      (node (ref "IC12") (pin "4") (pinfunction "V+_4") (pintype "power_in"))
      (node (ref "IC3") (pin "10") (pinfunction "EN2_10") (pintype "input"))
      (node (ref "IC3") (pin "16") (pinfunction "VDD2_16") (pintype "passive"))
      (node (ref "IC5") (pin "5") (pinfunction "OUT_5") (pintype "passive"))
      (node (ref "IC6") (pin "5") (pinfunction "V+_5") (pintype "power_in"))
      (node (ref "IC7") (pin "6") (pinfunction "VCC_6") (pintype "passive"))
      (node (ref "IC8") (pin "17") (pinfunction "VDD_2_17") (pintype "passive"))
      (node (ref "IC8") (pin "48") (pinfunction "VDD_1_48") (pintype "bidirectional"))
      (node (ref "JP1") (pin "1") (pinfunction "1_1") (pintype "passive"))
      (node (ref "JP2") (pin "1") (pinfunction "1_1") (pintype "passive"))
      (node (ref "NTC1") (pin "1") (pinfunction "P$1_1") (pintype "bidirectional"))
      (node (ref "NTC2") (pin "1") (pinfunction "P$1_1") (pintype "bidirectional"))
      (node (ref "Q10") (pin "2") (pinfunction "S_2") (pintype "passive"))
      (node (ref "Q5") (pin "2") (pinfunction "S_2") (pintype "passive"))
      (node (ref "R20") (pin "1") (pinfunction "1_1") (pintype "passive"))
      (node (ref "R23") (pin "1") (pinfunction "1_1") (pintype "passive"))
      (node (ref "TX_PU") (pin "2") (pinfunction "2_2") (pintype "passive"))
    )
    (net (code "2") (name "+8V") (class "Default")
      (node (ref "C14") (pin "1") (pinfunction "1_1") (pintype "passive"))
      (node (ref "C22") (pin "2") (pinfunction "2_2") (pintype "passive"))
      (node (ref "C45") (pin "1") (pinfunction "1_1") (pintype "passive"))
      (node (ref "D10") (pin "A") (pinfunction "A_A") (pintype "passive"))
      (node (ref "D5") (pin "A") (pinfunction "A_A") (pintype "passive"))
      (node (ref "IC10") (pin "8") (pinfunction "V+_8") (pintype "power_in"))
      (node (ref "IC5") (pin "1") (pinfunction "IN_1") (pintype "input"))
      (node (ref "IC5") (pin "3") (pinfunction "ON/~{OFF}_3") (pintype "input"))
      (node (ref "R4") (pin "1") (pinfunction "1_1") (pintype "passive"))
    )
    (net (code "3") (name "+VAUX") (class "Default")
      (node (ref "X2") (pin "2") (pinfunction "1_2") (pintype "passive"))
    )
    (net (code "4") (name "+VREF") (class "Default")
      (node (ref "C39") (pin "2") (pinfunction "2_2") (pintype "passive"))
      (node (ref "IC8") (pin "25") (pinfunction "VREFSD+_25") (pintype "passive"))
      (node (ref "IC8") (pin "9") (pinfunction "VDDA/VREF+_9") (pintype "passive"))
      (node (ref "IC9") (pin "1") (pinfunction "C_1") (pintype "passive"))
      (node (ref "IC9") (pin "2") (pinfunction "R_2") (pintype "passive"))
      (node (ref "R23") (pin "2") (pinfunction "2_2") (pintype "passive"))
    )
    (net (code "5") (name "-8V") (class "Default")
      (node (ref "C5") (pin "1") (pinfunction "1_1") (pintype "passive"))
      (node (ref "C51") (pin "2") (pinfunction "2_2") (pintype "passive"))
      (node (ref "IC10") (pin "4") (pinfunction "V-_4") (pintype "power_in"))
      (node (ref "R2") (pin "1") (pinfunction "1_1") (pintype "passive"))
    )
    (net (code "6") (name "AGND") (class "Default")
      (node (ref "C39") (pin "1") (pinfunction "1_1") (pintype "passive"))
      (node (ref "IC8") (pin "23") (pinfunction "VSSSD/VREFSD-_23") (pintype "passive"))
      (node (ref "IC8") (pin "8") (pinfunction "VSSA/VREF-_8") (pintype "passive"))
      (node (ref "IC9") (pin "3") (pinfunction "A_3") (pintype "passive"))
      (node (ref "SH2") (pin "1") (pinfunction "GND_A_1") (pintype "bidirectional"))
    )
    (net (code "7") (name "BOOT0") (class "Default")
      (node (ref "IC3") (pin "13") (pinfunction "B2_13") (pintype "output"))
      (node (ref "IC8") (pin "44") (pinfunction "BOOT0_44") (pintype "input"))
      (node (ref "JP1") (pin "2") (pinfunction "2_2") (pintype "passive"))
      (node (ref "R15") (pin "2") (pinfunction "2_2") (pintype "passive"))
    )
    (net (code "8") (name "CC#1") (class "Default")
      (node (ref "IC12") (pin "7") (pinfunction "OUT_7") (pintype "output"))
      (node (ref "IC8") (pin "3") (pinfunction "PC14-OSC32_IN_3") (pintype "bidirectional"))
    )
    (net (code "9") (name "CC#2") (class "Default")
      (node (ref "IC12") (pin "1") (pinfunction "OUT_1") (pintype "output"))
      (node (ref "IC8") (pin "4") (pinfunction "PC15-OSC32_OUT_4") (pintype "bidirectional"))
    )
    (net (code "10") (name "CC_LED#1") (class "Default")
      (node (ref "IC8") (pin "2") (pinfunction "PC13_2") (pintype "bidirectional"))
      (node (ref "Q5") (pin "1") (pinfunction "G_1") (pintype "passive"))
      (node (ref "R49") (pin "2") (pinfunction "2_2") (pintype "passive"))
    )
    (net (code "11") (name "CC_LED#2") (class "Default")
      (node (ref "IC8") (pin "11") (pinfunction "PA1_11") (pintype "bidirectional"))
      (node (ref "Q10") (pin "1") (pinfunction "G_1") (pintype "passive"))
      (node (ref "R73") (pin "2") (pinfunction "2_2") (pintype "passive"))
    )
    (net (code "12") (name "DC_OUT+") (class "Default")
      (node (ref "C3") (pin "2") (pinfunction "2_2") (pintype "passive"))
      (node (ref "C46") (pin "+") (pinfunction "+_+") (pintype "passive"))
      (node (ref "C50") (pin "1") (pinfunction "1_1") (pintype "passive"))
      (node (ref "C52") (pin "1") (pinfunction "1_1") (pintype "passive"))
      (node (ref "C6") (pin "1") (pinfunction "1_1") (pintype "passive"))
      (node (ref "C68") (pin "+") (pinfunction "+_+") (pintype "passive"))
      (node (ref "C71") (pin "1") (pinfunction "1_1") (pintype "passive"))
      (node (ref "C72") (pin "1") (pinfunction "1_1") (pintype "passive"))
      (node (ref "C9") (pin "1") (pinfunction "1_1") (pintype "passive"))
      (node (ref "IC11") (pin "6") (pinfunction "IVINN_6") (pintype "input"))
      (node (ref "IC11") (pin "7") (pinfunction "IVINP_7") (pintype "input"))
      (node (ref "IC13") (pin "6") (pinfunction "IVINN_6") (pintype "input"))
      (node (ref "IC13") (pin "7") (pinfunction "IVINP_7") (pintype "input"))
      (node (ref "IC2") (pin "2") (pinfunction "VIN_2") (pintype "power_in"))
      (node (ref "L1") (pin "4") (pinfunction "2_4") (pintype "passive"))
      (node (ref "Q2") (pin "2") (pinfunction "D_2") (pintype "passive"))
      (node (ref "Q7") (pin "2") (pinfunction "D_2") (pintype "passive"))
      (node (ref "R28") (pin "1") (pinfunction "1_1") (pintype "passive"))
      (node (ref "R29") (pin "1") (pinfunction "1_1") (pintype "passive"))
      (node (ref "R3") (pin "2") (pinfunction "2_2") (pintype "passive"))
      (node (ref "R52") (pin "1") (pinfunction "1_1") (pintype "passive"))
      (node (ref "R53") (pin "1") (pinfunction "1_1") (pintype "passive"))
      (node (ref "ZD1") (pin "C") (pinfunction "C_C") (pintype "passive"))
    )
    (net (code "13") (name "DIB_5V") (class "Default")
      (node (ref "X2") (pin "23") (pinfunction "1_23") (pintype "passive"))
      (node (ref "X2") (pin "24") (pinfunction "1_24") (pintype "passive"))
    )
    (net (code "14") (name "DIB_12V") (class "Default")
      (node (ref "X2") (pin "21") (pinfunction "1_21") (pintype "passive"))
      (node (ref "X2") (pin "22") (pinfunction "1_22") (pintype "passive"))
    )
    (net (code "15") (name "DIB_A0") (class "Default")
      (node (ref "IC4") (pin "1") (pinfunction "A0_1") (pintype "input"))
      (node (ref "R13") (pin "2") (pinfunction "2_2") (pintype "passive"))
      (node (ref "X2") (pin "17") (pinfunction "1_17") (pintype "passive"))
    )
    (net (code "16") (name "DIB_A1") (class "Default")
      (node (ref "IC4") (pin "2") (pinfunction "A1_2") (pintype "input"))
      (node (ref "R12") (pin "2") (pinfunction "2_2") (pintype "passive"))
      (node (ref "X2") (pin "19") (pinfunction "1_19") (pintype "passive"))
    )
    (net (code "17") (name "DIB_A2") (class "Default")
      (node (ref "IC4") (pin "3") (pinfunction "A2_3") (pintype "input"))
      (node (ref "R11") (pin "2") (pinfunction "2_2") (pintype "passive"))
      (node (ref "X2") (pin "18") (pinfunction "1_18") (pintype "passive"))
    )
    (net (code "18") (name "DIB_BOOT0") (class "Default")
      (node (ref "IC3") (pin "4") (pinfunction "A2_4") (pintype "input"))
      (node (ref "X2") (pin "26") (pinfunction "1_26") (pintype "passive"))
    )
    (net (code "19") (name "DIB_CSA") (class "Default")
      (node (ref "IC1") (pin "5") (pinfunction "A4_5") (pintype "input"))
      (node (ref "X2") (pin "9") (pinfunction "1_9") (pintype "passive"))
    )
    (net (code "20") (name "DIB_CSB") (class "Default")
      (node (ref "X2") (pin "12") (pinfunction "1_12") (pintype "passive"))
    )
    (net (code "21") (name "DIB_IRQ") (class "Default")
      (node (ref "IC1") (pin "7") (pinfunction "A6_7") (pintype "output"))
      (node (ref "X2") (pin "10") (pinfunction "1_10") (pintype "passive"))
    )
    (net (code "22") (name "DIB_MISO") (class "Default")
      (node (ref "IC1") (pin "6") (pinfunction "A5_6") (pintype "output"))
      (node (ref "X2") (pin "14") (pinfunction "1_14") (pintype "passive"))
    )
    (net (code "23") (name "DIB_MOSI") (class "Default")
      (node (ref "IC3") (pin "3") (pinfunction "A1_3") (pintype "input"))
      (node (ref "X2") (pin "15") (pinfunction "1_15") (pintype "passive"))
    )
    (net (code "24") (name "DIB_NFAULT") (class "Default")
      (node (ref "X2") (pin "3") (pinfunction "1_3") (pintype "passive"))
    )
    (net (code "25") (name "DIB_NRESET") (class "Default")
      (node (ref "IC1") (pin "2") (pinfunction "A1_2") (pintype "input"))
      (node (ref "X2") (pin "4") (pinfunction "1_4") (pintype "passive"))
    )
    (net (code "26") (name "DIB_SCL") (class "Default")
      (node (ref "IC4") (pin "6") (pinfunction "SCL_6") (pintype "bidirectional"))
      (node (ref "X2") (pin "5") (pinfunction "1_5") (pintype "passive"))
    )
    (net (code "27") (name "DIB_SCLK") (class "Default")
      (node (ref "IC1") (pin "4") (pinfunction "A3_4") (pintype "input"))
      (node (ref "X2") (pin "13") (pinfunction "1_13") (pintype "passive"))
    )
    (net (code "28") (name "DIB_SDA") (class "Default")
      (node (ref "IC4") (pin "5") (pinfunction "SDA_5") (pintype "bidirectional"))
      (node (ref "X2") (pin "8") (pinfunction "1_8") (pintype "passive"))
    )
    (net (code "29") (name "DIB_SYNC") (class "Default")
      (node (ref "IC1") (pin "3") (pinfunction "A2_3") (pintype "input"))
      (node (ref "X2") (pin "6") (pinfunction "1_6") (pintype "passive"))
    )
    (net (code "30") (name "DIB_UART_RX") (class "Default")
      (node (ref "IC3") (pin "6") (pinfunction "A4_6") (pintype "output"))
      (node (ref "X2") (pin "27") (pinfunction "1_27") (pintype "passive"))
    )
    (net (code "31") (name "DIB_UART_TX") (class "Default")
      (node (ref "IC3") (pin "5") (pinfunction "A3_5") (pintype "input"))
      (node (ref "X2") (pin "28") (pinfunction "1_28") (pintype "passive"))
    )
    (net (code "32") (name "FB1") (class "Default")
      (node (ref "IC11") (pin "11") (pinfunction "FB_11") (pintype "input"))
      (node (ref "IC12") (pin "10") (pinfunction "+IN_10") (pintype "input"))
      (node (ref "R39") (pin "1") (pinfunction "1_1") (pintype "passive"))
      (node (ref "R46") (pin "2") (pinfunction "2_2") (pintype "passive"))
      (node (ref "R48") (pin "2") (pinfunction "2_2") (pintype "passive"))
    )
    (net (code "33") (name "FB2") (class "Default")
      (node (ref "IC12") (pin "12") (pinfunction "+IN_12") (pintype "input"))
      (node (ref "IC13") (pin "11") (pinfunction "FB_11") (pintype "input"))
      (node (ref "R63") (pin "1") (pinfunction "1_1") (pintype "passive"))
      (node (ref "R70") (pin "2") (pinfunction "2_2") (pintype "passive"))
      (node (ref "R72") (pin "2") (pinfunction "2_2") (pintype "passive"))
    )
    (net (code "34") (name "GND") (class "Default")
      (node (ref "C12") (pin "2") (pinfunction "2_2") (pintype "passive"))
      (node (ref "C13") (pin "2") (pinfunction "2_2") (pintype "passive"))
      (node (ref "C14") (pin "2") (pinfunction "2_2") (pintype "passive"))
      (node (ref "C15") (pin "2") (pinfunction "2_2") (pintype "passive"))
      (node (ref "C16") (pin "1") (pinfunction "1_1") (pintype "passive"))
      (node (ref "C18") (pin "1") (pinfunction "1_1") (pintype "passive"))
      (node (ref "C19") (pin "1") (pinfunction "1_1") (pintype "passive"))
      (node (ref "C2") (pin "1") (pinfunction "1_1") (pintype "passive"))
      (node (ref "C21") (pin "2") (pinfunction "2_2") (pintype "passive"))
      (node (ref "C22") (pin "1") (pinfunction "1_1") (pintype "passive"))
      (node (ref "C23") (pin "1") (pinfunction "1_1") (pintype "passive"))
      (node (ref "C25") (pin "2") (pinfunction "2_2") (pintype "passive"))
      (node (ref "C26") (pin "2") (pinfunction "2_2") (pintype "passive"))
      (node (ref "C27") (pin "2") (pinfunction "2_2") (pintype "passive"))
      (node (ref "C28") (pin "1") (pinfunction "1_1") (pintype "passive"))
      (node (ref "C29") (pin "2") (pinfunction "2_2") (pintype "passive"))
      (node (ref "C31") (pin "2") (pinfunction "2_2") (pintype "passive"))
      (node (ref "C32") (pin "1") (pinfunction "1_1") (pintype "passive"))
      (node (ref "C33") (pin "1") (pinfunction "1_1") (pintype "passive"))
      (node (ref "C34") (pin "1") (pinfunction "1_1") (pintype "passive"))
      (node (ref "C35") (pin "1") (pinfunction "1_1") (pintype "passive"))
      (node (ref "C37") (pin "1") (pinfunction "1_1") (pintype "passive"))
      (node (ref "C38") (pin "1") (pinfunction "1_1") (pintype "passive"))
      (node (ref "C4") (pin "2") (pinfunction "2_2") (pintype "passive"))
      (node (ref "C40") (pin "1") (pinfunction "1_1") (pintype "passive"))
      (node (ref "C41") (pin "1") (pinfunction "1_1") (pintype "passive"))
      (node (ref "C42") (pin "1") (pinfunction "1_1") (pintype "passive"))
      (node (ref "C43") (pin "1") (pinfunction "1_1") (pintype "passive"))
      (node (ref "C44") (pin "1") (pinfunction "1_1") (pintype "passive"))
      (node (ref "C45") (pin "2") (pinfunction "2_2") (pintype "passive"))
      (node (ref "C46") (pin "-") (pinfunction "-_-") (pintype "passive"))
      (node (ref "C47") (pin "2") (pinfunction "2_2") (pintype "passive"))
      (node (ref "C49") (pin "2") (pinfunction "2_2") (pintype "passive"))
      (node (ref "C5") (pin "2") (pinfunction "2_2") (pintype "passive"))
      (node (ref "C50") (pin "2") (pinfunction "2_2") (pintype "passive"))
      (node (ref "C51") (pin "1") (pinfunction "1_1") (pintype "passive"))
      (node (ref "C52") (pin "2") (pinfunction "2_2") (pintype "passive"))
      (node (ref "C53") (pin "2") (pinfunction "2_2") (pintype "passive"))
      (node (ref "C55") (pin "2") (pinfunction "2_2") (pintype "passive"))
      (node (ref "C57") (pin "2") (pinfunction "2_2") (pintype "passive"))
      (node (ref "C59") (pin "2") (pinfunction "2_2") (pintype "passive"))
      (node (ref "C6") (pin "2") (pinfunction "2_2") (pintype "passive"))
      (node (ref "C60") (pin "2") (pinfunction "2_2") (pintype "passive"))
      (node (ref "C61") (pin "2") (pinfunction "-_2") (pintype "passive"))
      (node (ref "C62") (pin "-") (pinfunction "-_-") (pintype "passive"))
      (node (ref "C63") (pin "2") (pinfunction "2_2") (pintype "passive"))
      (node (ref "C64") (pin "1") (pinfunction "1_1") (pintype "passive"))
      (node (ref "C66") (pin "1") (pinfunction "1_1") (pintype "passive"))
      (node (ref "C68") (pin "-") (pinfunction "-_-") (pintype "passive"))
      (node (ref "C70") (pin "2") (pinfunction "2_2") (pintype "passive"))
      (node (ref "C71") (pin "2") (pinfunction "2_2") (pintype "passive"))
      (node (ref "C72") (pin "2") (pinfunction "2_2") (pintype "passive"))
      (node (ref "C73") (pin "2") (pinfunction "2_2") (pintype "passive"))
      (node (ref "C75") (pin "2") (pinfunction "2_2") (pintype "passive"))
      (node (ref "C77") (pin "2") (pinfunction "2_2") (pintype "passive"))
      (node (ref "C79") (pin "2") (pinfunction "2_2") (pintype "passive"))
      (node (ref "C8") (pin "1") (pinfunction "1_1") (pintype "passive"))
      (node (ref "C80") (pin "2") (pinfunction "2_2") (pintype "passive"))
      (node (ref "C81") (pin "2") (pinfunction "-_2") (pintype "passive"))
      (node (ref "C82") (pin "-") (pinfunction "-_-") (pintype "passive"))
      (node (ref "C83") (pin "2") (pinfunction "2_2") (pintype "passive"))
      (node (ref "C84") (pin "1") (pinfunction "1_1") (pintype "passive"))
      (node (ref "C86") (pin "1") (pinfunction "1_1") (pintype "passive"))
      (node (ref "C9") (pin "2") (pinfunction "2_2") (pintype "passive"))
      (node (ref "CH1") (pin "GND") (pinfunction "GND_GND") (pintype "bidirectional"))
      (node (ref "CH2") (pin "GND") (pinfunction "GND_GND") (pintype "bidirectional"))
      (node (ref "D12") (pin "A") (pinfunction "A_A") (pintype "passive"))
      (node (ref "D2") (pin "A") (pinfunction "A_A") (pintype "passive"))
      (node (ref "D7") (pin "A") (pinfunction "A_A") (pintype "passive"))
      (node (ref "GND") (pin "1") (pinfunction "P$1_1") (pintype "bidirectional"))
      (node (ref "IC1") (pin "9") (pinfunction "GND2_9") (pintype "passive"))
      (node (ref "IC11") (pin "12") (pinfunction "GND_12") (pintype "passive"))
      (node (ref "IC11") (pin "21") (pinfunction "SYNC_21") (pintype "input"))
      (node (ref "IC11") (pin "23") (pinfunction "GND_23") (pintype "passive"))
      (node (ref "IC11") (pin "28") (pinfunction "GND_28") (pintype "passive"))
      (node (ref "IC11") (pin "TP") (pinfunction "GND_PAD_TP") (pintype "passive"))
      (node (ref "IC12") (pin "11") (pinfunction "V-_11") (pintype "power_in"))
      (node (ref "IC13") (pin "12") (pinfunction "GND_12") (pintype "passive"))
      (node (ref "IC13") (pin "21") (pinfunction "SYNC_21") (pintype "input"))
      (node (ref "IC13") (pin "23") (pinfunction "GND_23") (pintype "passive"))
      (node (ref "IC13") (pin "28") (pinfunction "GND_28") (pintype "passive"))
      (node (ref "IC13") (pin "TP") (pinfunction "GND_PAD_TP") (pintype "passive"))
      (node (ref "IC2") (pin "9") (pinfunction "GND_9") (pintype "passive"))
      (node (ref "IC2") (pin "TP") (pinfunction "TP_TP") (pintype "passive"))
      (node (ref "IC3") (pin "15") (pinfunction "GND2_15") (pintype "passive"))
      (node (ref "IC3") (pin "9") (pinfunction "GND2_2_9") (pintype "passive"))
      (node (ref "IC5") (pin "2") (pinfunction "GND_2") (pintype "passive"))
      (node (ref "IC6") (pin "2") (pinfunction "V-_2") (pintype "power_in"))
      (node (ref "IC7") (pin "3") (pinfunction "GND_3") (pintype "power_in"))
      (node (ref "IC8") (pin "47") (pinfunction "VSS_1_47") (pintype "bidirectional"))
      (node (ref "J3") (pin "1") (pinfunction "1_1") (pintype "passive"))
      (node (ref "J3") (pin "1.1") (pinfunction "1_1.1") (pintype "passive"))
      (node (ref "J5") (pin "1") (pinfunction "1_1") (pintype "passive"))
      (node (ref "J5") (pin "1.1") (pinfunction "1_1.1") (pintype "passive"))
      (node (ref "L1") (pin "2") (pinfunction "2_2") (pintype "passive"))
      (node (ref "LED1") (pin "CC") (pinfunction "C_CC") (pintype "passive"))
      (node (ref "LED2") (pin "CC") (pinfunction "C_CC") (pintype "passive"))
      (node (ref "Q3") (pin "3") (pinfunction "S_3") (pintype "passive"))
      (node (ref "Q8") (pin "3") (pinfunction "S_3") (pintype "passive"))
      (node (ref "R10") (pin "1") (pinfunction "1_1") (pintype "passive"))
      (node (ref "R15") (pin "1") (pinfunction "1_1") (pintype "passive"))
      (node (ref "R19") (pin "1") (pinfunction "1_1") (pintype "passive"))
      (node (ref "R21") (pin "2") (pinfunction "2_2") (pintype "passive"))
      (node (ref "R22") (pin "2") (pinfunction "2_2") (pintype "passive"))
      (node (ref "R30") (pin "1") (pinfunction "1_1") (pintype "passive"))
      (node (ref "R33") (pin "1") (pinfunction "1_1") (pintype "passive"))
      (node (ref "R37") (pin "1") (pinfunction "1_1") (pintype "passive"))
      (node (ref "R41") (pin "2") (pinfunction "2_2") (pintype "passive"))
      (node (ref "R42") (pin "1") (pinfunction "1_1") (pintype "passive"))
      (node (ref "R45") (pin "1") (pinfunction "1_1") (pintype "passive"))
      (node (ref "R46") (pin "1") (pinfunction "1_1") (pintype "passive"))
      (node (ref "R47") (pin "1") (pinfunction "1_1") (pintype "passive"))
      (node (ref "R5") (pin "1") (pinfunction "1_1") (pintype "passive"))
      (node (ref "R51") (pin "1") (pinfunction "1_1") (pintype "passive"))
      (node (ref "R54") (pin "1") (pinfunction "1_1") (pintype "passive"))
      (node (ref "R57") (pin "1") (pinfunction "1_1") (pintype "passive"))
      (node (ref "R6") (pin "1") (pinfunction "1_1") (pintype "passive"))
      (node (ref "R61") (pin "1") (pinfunction "1_1") (pintype "passive"))
      (node (ref "R65") (pin "2") (pinfunction "2_2") (pintype "passive"))
      (node (ref "R66") (pin "1") (pinfunction "1_1") (pintype "passive"))
      (node (ref "R69") (pin "1") (pinfunction "1_1") (pintype "passive"))
      (node (ref "R70") (pin "1") (pinfunction "1_1") (pintype "passive"))
      (node (ref "R71") (pin "1") (pinfunction "1_1") (pintype "passive"))
      (node (ref "R75") (pin "1") (pinfunction "1_1") (pintype "passive"))
      (node (ref "R8") (pin "1") (pinfunction "1_1") (pintype "passive"))
      (node (ref "SH2") (pin "2") (pinfunction "GND_B_2") (pintype "bidirectional"))
      (node (ref "TR1") (pin "4") (pinfunction "4_4") (pintype "passive"))
      (node (ref "X3") (pin "3") (pinfunction "S_3") (pintype "passive"))
      (node (ref "X4") (pin "1") (pinfunction "1_1") (pintype "passive"))
      (node (ref "X4") (pin "10") (pinfunction "1_10") (pintype "passive"))
      (node (ref "X4") (pin "2") (pinfunction "1_2") (pintype "passive"))
      (node (ref "X4") (pin "3") (pinfunction "1_3") (pintype "passive"))
      (node (ref "X4") (pin "4") (pinfunction "1_4") (pintype "passive"))
      (node (ref "X4") (pin "5") (pinfunction "1_5") (pintype "passive"))
      (node (ref "X4") (pin "6") (pinfunction "1_6") (pintype "passive"))
      (node (ref "X4") (pin "7") (pinfunction "1_7") (pintype "passive"))
      (node (ref "X4") (pin "8") (pinfunction "1_8") (pintype "passive"))
      (node (ref "X4") (pin "9") (pinfunction "1_9") (pintype "passive"))
      (node (ref "ZD1") (pin "A") (pinfunction "A_A") (pintype "passive"))
      (node (ref "ZD3") (pin "A") (pinfunction "A_A") (pintype "passive"))
      (node (ref "ZD5") (pin "A") (pinfunction "A_A") (pintype "passive"))
    )
    (net (code "35") (name "GNDIO") (class "Default")
      (node (ref "C17") (pin "2") (pinfunction "2_2") (pintype "passive"))
      (node (ref "C20") (pin "1") (pinfunction "1_1") (pintype "passive"))
      (node (ref "C7") (pin "2") (pinfunction "2_2") (pintype "passive"))
      (node (ref "IC1") (pin "8") (pinfunction "GND1_8") (pintype "passive"))
      (node (ref "IC3") (pin "2") (pinfunction "GND1_2_2") (pintype "passive"))
      (node (ref "IC3") (pin "8") (pinfunction "GND1_8") (pintype "passive"))
      (node (ref "IC4") (pin "4") (pinfunction "GND_4") (pintype "passive"))
      (node (ref "IC4") (pin "7") (pinfunction "WP_7") (pintype "input"))
      (node (ref "X2") (pin "11") (pinfunction "1_11") (pintype "passive"))
      (node (ref "X2") (pin "16") (pinfunction "1_16") (pintype "passive"))
      (node (ref "X2") (pin "20") (pinfunction "1_20") (pintype "passive"))
      (node (ref "X2") (pin "25") (pinfunction "1_25") (pintype "passive"))
      (node (ref "X2") (pin "7") (pinfunction "1_7") (pintype "passive"))
    )
    (net (code "36") (name "INTVCC1") (class "Default")
      (node (ref "C55") (pin "1") (pinfunction "1_1") (pintype "passive"))
      (node (ref "D6") (pin "A") (pinfunction "A_A") (pintype "passive"))
      (node (ref "IC11") (pin "2") (pinfunction "INTVCC_2") (pintype "passive"))
      (node (ref "R43") (pin "1") (pinfunction "1_1") (pintype "passive"))
      (node (ref "R44") (pin "2") (pinfunction "2_2") (pintype "passive"))
    )
    (net (code "37") (name "INTVCC2") (class "Default")
      (node (ref "C75") (pin "1") (pinfunction "1_1") (pintype "passive"))
      (node (ref "D11") (pin "A") (pinfunction "A_A") (pintype "passive"))
      (node (ref "IC13") (pin "2") (pinfunction "INTVCC_2") (pintype "passive"))
      (node (ref "R67") (pin "1") (pinfunction "1_1") (pintype "passive"))
      (node (ref "R68") (pin "2") (pinfunction "2_2") (pintype "passive"))
    )
    (net (code "38") (name "IRQ") (class "Default")
      (node (ref "IC1") (pin "10") (pinfunction "B6_10") (pintype "input"))
      (node (ref "IC8") (pin "33") (pinfunction "PA12_33") (pintype "bidirectional"))
    )
    (net (code "39") (name "I_MON#1") (class "Default")
      (node (ref "C42") (pin "2") (pinfunction "2_2") (pintype "passive"))
      (node (ref "IC8") (pin "19") (pinfunction "PB1_19") (pintype "bidirectional"))
      (node (ref "R25") (pin "1") (pinfunction "1_1") (pintype "passive"))
    )
    (net (code "40") (name "I_MON#2") (class "Default")
      (node (ref "C44") (pin "2") (pinfunction "2_2") (pintype "passive"))
      (node (ref "IC8") (pin "21") (pinfunction "PE8_21") (pintype "bidirectional"))
      (node (ref "R27") (pin "1") (pinfunction "1_1") (pintype "passive"))
    )
    (net (code "41") (name "I_MON1") (class "Default")
      (node (ref "C64") (pin "2") (pinfunction "2_2") (pintype "passive"))
      (node (ref "R25") (pin "2") (pinfunction "2_2") (pintype "passive"))
      (node (ref "R38") (pin "1") (pinfunction "1_1") (pintype "passive"))
    )
    (net (code "42") (name "I_MON2") (class "Default")
      (node (ref "C84") (pin "2") (pinfunction "2_2") (pintype "passive"))
      (node (ref "R27") (pin "2") (pinfunction "2_2") (pintype "passive"))
      (node (ref "R62") (pin "1") (pinfunction "1_1") (pintype "passive"))
    )
    (net (code "43") (name "I_SET#1") (class "Default")
      (node (ref "I_SET1") (pin "1") (pinfunction "1_1") (pintype "passive"))
      (node (ref "R32") (pin "1") (pinfunction "1_1") (pintype "passive"))
    )
    (net (code "44") (name "I_SET#2") (class "Default")
      (node (ref "I_SET2") (pin "1") (pinfunction "1_1") (pintype "passive"))
      (node (ref "R56") (pin "1") (pinfunction "1_1") (pintype "passive"))
    )
    (net (code "45") (name "I_SET_OUT#1") (class "Default")
      (node (ref "IC6") (pin "1") (pinfunction "I_1") (pintype "input"))
      (node (ref "IC8") (pin "45") (pinfunction "PB8_45") (pintype "bidirectional"))
      (node (ref "R14") (pin "2") (pinfunction "2_2") (pintype "passive"))
    )
    (net (code "46") (name "I_SET_OUT#2") (class "Default")
      (node (ref "IC6") (pin "3") (pinfunction "I_3") (pintype "input"))
      (node (ref "IC8") (pin "46") (pinfunction "PB9_46") (pintype "bidirectional"))
      (node (ref "R17") (pin "2") (pinfunction "2_2") (pintype "passive"))
    )
    (net (code "47") (name "MISO") (class "Default")
      (node (ref "IC1") (pin "11") (pinfunction "B5_11") (pintype "input"))
      (node (ref "IC8") (pin "26") (pinfunction "PB14_26") (pintype "bidirectional"))
    )
    (net (code "48") (name "MOSI") (class "Default")
      (node (ref "IC8") (pin "27") (pinfunction "PB15_27") (pintype "bidirectional"))
      (node (ref "RN1") (pin "5") (pinfunction "2_5") (pintype "passive"))
    )
    (net (code "49") (name "NRST") (class "Default")
      (node (ref "C36") (pin "1") (pinfunction "1_1") (pintype "passive"))
      (node (ref "IC8") (pin "7") (pinfunction "NRST_7") (pintype "input"))
      (node (ref "JP3") (pin "2") (pinfunction "2_2") (pintype "passive"))
      (node (ref "R20") (pin "2") (pinfunction "2_2") (pintype "passive"))
      (node (ref "RN2") (pin "3") (pinfunction "1_3") (pintype "passive"))
    )
    (net (code "50") (name "NSS") (class "Default")
      (node (ref "IC8") (pin "32") (pinfunction "PA11_32") (pintype "bidirectional"))
      (node (ref "RN1") (pin "6") (pinfunction "2_6") (pintype "passive"))
    )
    (net (code "51") (name "Net-(C4-Pad1)") (class "Default")
      (node (ref "C4") (pin "1") (pinfunction "1_1") (pintype "passive"))
      (node (ref "D1") (pin "A") (pinfunction "A_A") (pintype "passive"))
      (node (ref "R2") (pin "2") (pinfunction "2_2") (pintype "passive"))
    )
    (net (code "52") (name "Net-(C11-Pad2)") (class "Default")
      (node (ref "C11") (pin "2") (pinfunction "2_2") (pintype "passive"))
      (node (ref "R5") (pin "2") (pinfunction "2_2") (pintype "passive"))
    )
    (net (code "53") (name "Net-(C12-Pad1)") (class "Default")
      (node (ref "C12") (pin "1") (pinfunction "1_1") (pintype "passive"))
      (node (ref "C13") (pin "1") (pinfunction "1_1") (pintype "passive"))
      (node (ref "R4") (pin "2") (pinfunction "2_2") (pintype "passive"))
      (node (ref "R7") (pin "2") (pinfunction "2_2") (pintype "passive"))
      (node (ref "TR1") (pin "3") (pinfunction "3_3") (pintype "passive"))
    )
    (net (code "54") (name "Net-(C19-Pad2)") (class "Default")
      (node (ref "C19") (pin "2") (pinfunction "2_2") (pintype "passive"))
      (node (ref "R9") (pin "1") (pinfunction "1_1") (pintype "passive"))
    )
    (net (code "55") (name "Net-(C24-Pad1)") (class "Default")
      (node (ref "C24") (pin "1") (pinfunction "1_1") (pintype "passive"))
      (node (ref "C26") (pin "1") (pinfunction "1_1") (pintype "passive"))
      (node (ref "I_SET1") (pin "2") (pinfunction "2_2") (pintype "passive"))
      (node (ref "R14") (pin "1") (pinfunction "1_1") (pintype "passive"))
    )
    (net (code "56") (name "Net-(C24-Pad2)") (class "Default")
      (node (ref "C24") (pin "2") (pinfunction "2_2") (pintype "passive"))
      (node (ref "R16") (pin "1") (pinfunction "1_1") (pintype "passive"))
    )
    (net (code "57") (name "Net-(C30-Pad1)") (class "Default")
      (node (ref "C30") (pin "1") (pinfunction "1_1") (pintype "passive"))
      (node (ref "C31") (pin "1") (pinfunction "1_1") (pintype "passive"))
      (node (ref "I_SET2") (pin "2") (pinfunction "2_2") (pintype "passive"))
      (node (ref "R17") (pin "1") (pinfunction "1_1") (pintype "passive"))
    )
    (net (code "58") (name "Net-(C30-Pad2)") (class "Default")
      (node (ref "C30") (pin "2") (pinfunction "2_2") (pintype "passive"))
      (node (ref "R18") (pin "1") (pinfunction "1_1") (pintype "passive"))
    )
    (net (code "59") (name "Net-(C58-Pad2)") (class "Default")
      (node (ref "C58") (pin "2") (pinfunction "2_2") (pintype "passive"))
      (node (ref "R37") (pin "2") (pinfunction "2_2") (pintype "passive"))
    )
    (net (code "60") (name "Net-(C67-Pad1)") (class "Default")
      (node (ref "C67") (pin "1") (pinfunction "1_1") (pintype "passive"))
      (node (ref "R45") (pin "2") (pinfunction "2_2") (pintype "passive"))
    )
    (net (code "61") (name "Net-(C78-Pad2)") (class "Default")
      (node (ref "C78") (pin "2") (pinfunction "2_2") (pintype "passive"))
      (node (ref "R61") (pin "2") (pinfunction "2_2") (pintype "passive"))
    )
    (net (code "62") (name "Net-(C87-Pad1)") (class "Default")
      (node (ref "C87") (pin "1") (pinfunction "1_1") (pintype "passive"))
      (node (ref "R69") (pin "2") (pinfunction "2_2") (pintype "passive"))
    )
    (net (code "63") (name "Net-(D1-PadC)") (class "Default")
      (node (ref "D1") (pin "C") (pinfunction "C_C") (pintype "passive"))
      (node (ref "TR1") (pin "2") (pinfunction "2_2") (pintype "passive"))
    )
    (net (code "64") (name "Net-(IC1-B2)") (class "Default")
      (node (ref "IC1") (pin "14") (pinfunction "B2_14") (pintype "output"))
      (node (ref "RN1") (pin "1") (pinfunction "1_1") (pintype "passive"))
    )
    (net (code "65") (name "Net-(IC1-B3)") (class "Default")
      (node (ref "IC1") (pin "13") (pinfunction "B3_13") (pintype "output"))
      (node (ref "RN1") (pin "2") (pinfunction "1_2") (pintype "passive"))
    )
    (net (code "66") (name "Net-(IC1-B4)") (class "Default")
      (node (ref "IC1") (pin "12") (pinfunction "B4_12") (pintype "output"))
      (node (ref "RN1") (pin "3") (pinfunction "1_3") (pintype "passive"))
    )
    (net (code "67") (name "Net-(IC2-BOOT)") (class "Default")
      (node (ref "C10") (pin "2") (pinfunction "2_2") (pintype "passive"))
      (node (ref "IC2") (pin "1") (pinfunction "BOOT_1") (pintype "output"))
    )
    (net (code "68") (name "Net-(IC2-COMP)") (class "Default")
      (node (ref "C16") (pin "2") (pinfunction "2_2") (pintype "passive"))
      (node (ref "IC2") (pin "8") (pinfunction "COMP_8") (pintype "output"))
      (node (ref "R9") (pin "2") (pinfunction "2_2") (pintype "passive"))
    )
    (net (code "69") (name "Net-(IC2-EN)") (class "Default")
      (node (ref "IC2") (pin "3") (pinfunction "EN_3") (pintype "input"))
      (node (ref "R3") (pin "1") (pinfunction "1_1") (pintype "passive"))
      (node (ref "R6") (pin "2") (pinfunction "2_2") (pintype "passive"))
    )
    (net (code "70") (name "Net-(IC2-PH)") (class "Default")
      (node (ref "C10") (pin "1") (pinfunction "1_1") (pintype "passive"))
      (node (ref "C11") (pin "1") (pinfunction "1_1") (pintype "passive"))
      (node (ref "D2") (pin "C") (pinfunction "C_C") (pintype "passive"))
      (node (ref "IC2") (pin "10") (pinfunction "PH_10") (pintype "input"))
      (node (ref "TR1") (pin "1") (pinfunction "1_1") (pintype "passive"))
    )
    (net (code "71") (name "Net-(IC2-RT{slash}CLK)") (class "Default")
      (node (ref "IC2") (pin "5") (pinfunction "RT/CLK_5") (pintype "input"))
      (node (ref "R8") (pin "2") (pinfunction "2_2") (pintype "passive"))
    )
    (net (code "72") (name "Net-(IC2-SS{slash}TR)") (class "Default")
      (node (ref "C15") (pin "1") (pinfunction "1_1") (pintype "passive"))
      (node (ref "IC2") (pin "4") (pinfunction "SS/TR_4") (pintype "input"))
    )
    (net (code "73") (name "Net-(IC2-VSENSE)") (class "Default")
      (node (ref "IC2") (pin "7") (pinfunction "VSENSE_7") (pintype "input"))
      (node (ref "R10") (pin "2") (pinfunction "2_2") (pintype "passive"))
      (node (ref "R7") (pin "1") (pinfunction "1_1") (pintype "passive"))
    )
    (net (code "74") (name "Net-(IC3-B1)") (class "Default")
      (node (ref "IC3") (pin "14") (pinfunction "B1_14") (pintype "output"))
      (node (ref "RN1") (pin "4") (pinfunction "1_4") (pintype "passive"))
    )
    (net (code "75") (name "Net-(IC5-BYPASS)") (class "Default")
      (node (ref "C23") (pin "2") (pinfunction "2_2") (pintype "passive"))
      (node (ref "IC5") (pin "4") (pinfunction "BYPASS_4") (pintype "passive"))
    )
    (net (code "76") (name "Net-(IC6A-O)") (class "Default")
      (node (ref "IC6") (pin "6") (pinfunction "O_6") (pintype "output"))
      (node (ref "R16") (pin "2") (pinfunction "2_2") (pintype "passive"))
    )
    (net (code "77") (name "Net-(IC6B-O)") (class "Default")
      (node (ref "IC6") (pin "4") (pinfunction "O_4") (pintype "output"))
      (node (ref "R18") (pin "2") (pinfunction "2_2") (pintype "passive"))
    )
    (net (code "78") (name "Net-(IC7-IO1)") (class "Default")
      (node (ref "IC7") (pin "1") (pinfunction "IO1_1") (pintype "bidirectional"))
      (node (ref "RN2") (pin "8") (pinfunction "2_8") (pintype "passive"))
      (node (ref "X3") (pin "6") (pinfunction "S_6") (pintype "passive"))
    )
    (net (code "79") (name "Net-(IC7-IO2)") (class "Default")
      (node (ref "IC7") (pin "2") (pinfunction "IO2_2") (pintype "bidirectional"))
      (node (ref "RN2") (pin "6") (pinfunction "2_6") (pintype "passive"))
      (node (ref "X3") (pin "5") (pinfunction "S_5") (pintype "passive"))
    )
    (net (code "80") (name "Net-(IC8-PB5)") (class "Default")
      (node (ref "IC8") (pin "41") (pinfunction "PB5_41") (pintype "bidirectional"))
      (node (ref "OE#1") (pin "1") (pinfunction "1_1") (pintype "passive"))
    )
    (net (code "81") (name "Net-(IC8-PB6)") (class "Default")
      (node (ref "IC8") (pin "42") (pinfunction "PB6_42") (pintype "bidirectional"))
      (node (ref "OE#2") (pin "1") (pinfunction "1_1") (pintype "passive"))
    )
    (net (code "82") (name "Net-(IC8-PF0-OSC_IN)") (class "Default")
      (node (ref "C32") (pin "2") (pinfunction "2_2") (pintype "passive"))
      (node (ref "IC8") (pin "5") (pinfunction "PF0-OSC_IN_5") (pintype "bidirectional"))
      (node (ref "Y1") (pin "3") (pinfunction "2_3") (pintype "passive"))
    )
    (net (code "83") (name "Net-(IC8-PF1-OSC_OUT)") (class "Default")
      (node (ref "C33") (pin "2") (pinfunction "2_2") (pintype "passive"))
      (node (ref "IC8") (pin "6") (pinfunction "PF1-OSC_OUT_6") (pintype "bidirectional"))
      (node (ref "Y1") (pin "1") (pinfunction "1_1") (pintype "passive"))
    )
    (net (code "84") (name "Net-(IC10A-+IN)") (class "Default")
      (node (ref "IC10") (pin "3") (pinfunction "+IN_3") (pintype "input"))
      (node (ref "R56") (pin "2") (pinfunction "2_2") (pintype "passive"))
      (node (ref "R57") (pin "2") (pinfunction "2_2") (pintype "passive"))
    )
    (net (code "85") (name "Net-(IC10A--IN)") (class "Default")
      (node (ref "C69") (pin "2") (pinfunction "2_2") (pintype "passive"))
      (node (ref "IC10") (pin "2") (pinfunction "-IN_2") (pintype "input"))
      (node (ref "R54") (pin "2") (pinfunction "2_2") (pintype "passive"))
      (node (ref "R55") (pin "1") (pinfunction "1_1") (pintype "passive"))
    )
    (net (code "86") (name "Net-(IC10A-OUT)") (class "Default")
      (node (ref "C69") (pin "1") (pinfunction "1_1") (pintype "passive"))
      (node (ref "IC10") (pin "1") (pinfunction "OUT_1") (pintype "output"))
      (node (ref "IC13") (pin "14") (pinfunction "CTRL1_14") (pintype "input"))
      (node (ref "R55") (pin "2") (pinfunction "2_2") (pintype "passive"))
    )
    (net (code "87") (name "Net-(IC10B-+IN)") (class "Default")
      (node (ref "IC10") (pin "5") (pinfunction "+IN_5") (pintype "input"))
      (node (ref "R32") (pin "2") (pinfunction "2_2") (pintype "passive"))
      (node (ref "R33") (pin "2") (pinfunction "2_2") (pintype "passive"))
    )
    (net (code "88") (name "Net-(IC10B--IN)") (class "Default")
      (node (ref "C48") (pin "2") (pinfunction "2_2") (pintype "passive"))
      (node (ref "IC10") (pin "6") (pinfunction "-IN_6") (pintype "input"))
      (node (ref "R30") (pin "2") (pinfunction "2_2") (pintype "passive"))
      (node (ref "R31") (pin "1") (pinfunction "1_1") (pintype "passive"))
    )
    (net (code "89") (name "Net-(IC10B-OUT)") (class "Default")
      (node (ref "C48") (pin "1") (pinfunction "1_1") (pintype "passive"))
      (node (ref "IC10") (pin "7") (pinfunction "OUT_7") (pintype "output"))
      (node (ref "IC11") (pin "14") (pinfunction "CTRL1_14") (pintype "input"))
      (node (ref "R31") (pin "2") (pinfunction "2_2") (pintype "passive"))
    )
    (net (code "90") (name "Net-(IC11-BG)") (class "Default")
      (node (ref "IC11") (pin "1") (pinfunction "BG_1") (pintype "output"))
      (node (ref "Q3") (pin "1") (pinfunction "G_1") (pintype "passive"))
    )
    (net (code "91") (name "Net-(IC11-BOOST)") (class "Default")
      (node (ref "C54") (pin "1") (pinfunction "1_1") (pintype "passive"))
      (node (ref "D6") (pin "C") (pinfunction "C_C") (pintype "passive"))
      (node (ref "IC11") (pin "27") (pinfunction "BOOST_27") (pintype "passive"))
    )
    (net (code "92") (name "Net-(IC11-ISMON)") (class "Default")
      (node (ref "IC11") (pin "19") (pinfunction "ISMON_19") (pintype "output"))
      (node (ref "R38") (pin "2") (pinfunction "2_2") (pintype "passive"))
    )
    (net (code "93") (name "Net-(IC11-PWM)") (class "Default")
      (node (ref "IC11") (pin "22") (pinfunction "PWM_22") (pintype "input"))
      (node (ref "R43") (pin "2") (pinfunction "2_2") (pintype "passive"))
    )
    (net (code "94") (name "Net-(IC11-RT)") (class "Default")
      (node (ref "IC11") (pin "20") (pinfunction "RT_20") (pintype "input"))
      (node (ref "R42") (pin "2") (pinfunction "2_2") (pintype "passive"))
    )
    (net (code "95") (name "Net-(IC11-SENSE+)") (class "Default")
      (node (ref "C65") (pin "1") (pinfunction "1_1") (pintype "passive"))
      (node (ref "IC11") (pin "17") (pinfunction "SENSE+_17") (pintype "input"))
      (node (ref "R35") (pin "1") (pinfunction "1_1") (pintype "passive"))
    )
    (net (code "96") (name "Net-(IC11-SENSE-)") (class "Default")
      (node (ref "C65") (pin "2") (pinfunction "2_2") (pintype "passive"))
      (node (ref "IC11") (pin "16") (pinfunction "SENSE-_16") (pintype "input"))
      (node (ref "R36") (pin "1") (pinfunction "1_1") (pintype "passive"))
    )
    (net (code "97") (name "Net-(IC11-SS)") (class "Default")
      (node (ref "C66") (pin "2") (pinfunction "2_2") (pintype "passive"))
      (node (ref "IC11") (pin "15") (pinfunction "SS_15") (pintype "input"))
    )
    (net (code "98") (name "Net-(IC11-SW)") (class "Default")
      (node (ref "C54") (pin "2") (pinfunction "2_2") (pintype "passive"))
      (node (ref "C58") (pin "1") (pinfunction "1_1") (pintype "passive"))
      (node (ref "D7") (pin "C") (pinfunction "C_C") (pintype "passive"))
      (node (ref "IC11") (pin "26") (pinfunction "SW_26") (pintype "output"))
      (node (ref "L2") (pin "1") (pinfunction "1_1") (pintype "passive"))
      (node (ref "Q2") (pin "3") (pinfunction "S_3") (pintype "passive"))
      (node (ref "Q3") (pin "2") (pinfunction "D_2") (pintype "passive"))
    )
    (net (code "99") (name "Net-(IC11-TG)") (class "Default")
      (node (ref "IC11") (pin "25") (pinfunction "TG_25") (pintype "output"))
      (node (ref "Q2") (pin "1") (pinfunction "G_1") (pintype "passive"))
    )
    (net (code "100") (name "Net-(IC11-VC)") (class "Default")
      (node (ref "C67") (pin "2") (pinfunction "2_2") (pintype "passive"))
      (node (ref "IC11") (pin "18") (pinfunction "VC_18") (pintype "passive"))
    )
    (net (code "101") (name "Net-(IC11-VIN)") (class "Default")
      (node (ref "C49") (pin "1") (pinfunction "1_1") (pintype "passive"))
      (node (ref "D3") (pin "C") (pinfunction "C_C") (pintype "passive"))
      (node (ref "D5") (pin "C") (pinfunction "C_C") (pintype "passive"))
      (node (ref "IC11") (pin "3") (pinfunction "VIN_3") (pintype "passive"))
    )
    (net (code "102") (name "Net-(IC11-~{FAULT})") (class "Default")
      (node (ref "IC11") (pin "9") (pinfunction "~{FAULT}_9") (pintype "output"))
      (node (ref "R44") (pin "1") (pinfunction "1_1") (pintype "passive"))
    )
    (net (code "103") (name "Net-(IC12A-+IN)") (class "Default")
      (node (ref "IC12") (pin "3") (pinfunction "+IN_3") (pintype "input"))
      (node (ref "R74") (pin "1") (pinfunction "1_1") (pintype "passive"))
      (node (ref "R75") (pin "2") (pinfunction "2_2") (pintype "passive"))
    )
    (net (code "104") (name "Net-(IC12A--IN)") (class "Default")
      (node (ref "IC12") (pin "13") (pinfunction "-IN_13") (pintype "input"))
      (node (ref "IC12") (pin "14") (pinfunction "OUT_14") (pintype "output"))
      (node (ref "IC12") (pin "2") (pinfunction "-IN_2") (pintype "input"))
    )
    (net (code "105") (name "Net-(IC12B-+IN)") (class "Default")
      (node (ref "IC12") (pin "5") (pinfunction "+IN_5") (pintype "input"))
      (node (ref "R50") (pin "1") (pinfunction "1_1") (pintype "passive"))
      (node (ref "R51") (pin "2") (pinfunction "2_2") (pintype "passive"))
    )
    (net (code "106") (name "Net-(IC12B--IN)") (class "Default")
      (node (ref "IC12") (pin "6") (pinfunction "-IN_6") (pintype "input"))
      (node (ref "IC12") (pin "8") (pinfunction "OUT_8") (pintype "output"))
      (node (ref "IC12") (pin "9") (pinfunction "-IN_9") (pintype "input"))
    )
    (net (code "107") (name "Net-(IC13-BG)") (class "Default")
      (node (ref "IC13") (pin "1") (pinfunction "BG_1") (pintype "output"))
      (node (ref "Q8") (pin "1") (pinfunction "G_1") (pintype "passive"))
    )
    (net (code "108") (name "Net-(IC13-BOOST)") (class "Default")
      (node (ref "C74") (pin "1") (pinfunction "1_1") (pintype "passive"))
      (node (ref "D11") (pin "C") (pinfunction "C_C") (pintype "passive"))
      (node (ref "IC13") (pin "27") (pinfunction "BOOST_27") (pintype "passive"))
    )
    (net (code "109") (name "Net-(IC13-ISMON)") (class "Default")
      (node (ref "IC13") (pin "19") (pinfunction "ISMON_19") (pintype "output"))
      (node (ref "R62") (pin "2") (pinfunction "2_2") (pintype "passive"))
    )
    (net (code "110") (name "Net-(IC13-PWM)") (class "Default")
      (node (ref "IC13") (pin "22") (pinfunction "PWM_22") (pintype "input"))
      (node (ref "R67") (pin "2") (pinfunction "2_2") (pintype "passive"))
    )
    (net (code "111") (name "Net-(IC13-RT)") (class "Default")
      (node (ref "IC13") (pin "20") (pinfunction "RT_20") (pintype "input"))
      (node (ref "R66") (pin "2") (pinfunction "2_2") (pintype "passive"))
    )
    (net (code "112") (name "Net-(IC13-SENSE+)") (class "Default")
      (node (ref "C85") (pin "1") (pinfunction "1_1") (pintype "passive"))
      (node (ref "IC13") (pin "17") (pinfunction "SENSE+_17") (pintype "input"))
      (node (ref "R59") (pin "1") (pinfunction "1_1") (pintype "passive"))
    )
    (net (code "113") (name "Net-(IC13-SENSE-)") (class "Default")
      (node (ref "C85") (pin "2") (pinfunction "2_2") (pintype "passive"))
      (node (ref "IC13") (pin "16") (pinfunction "SENSE-_16") (pintype "input"))
      (node (ref "R60") (pin "1") (pinfunction "1_1") (pintype "passive"))
    )
    (net (code "114") (name "Net-(IC13-SS)") (class "Default")
      (node (ref "C86") (pin "2") (pinfunction "2_2") (pintype "passive"))
      (node (ref "IC13") (pin "15") (pinfunction "SS_15") (pintype "input"))
    )
    (net (code "115") (name "Net-(IC13-SW)") (class "Default")
      (node (ref "C74") (pin "2") (pinfunction "2_2") (pintype "passive"))
      (node (ref "C78") (pin "1") (pinfunction "1_1") (pintype "passive"))
      (node (ref "D12") (pin "C") (pinfunction "C_C") (pintype "passive"))
      (node (ref "IC13") (pin "26") (pinfunction "SW_26") (pintype "output"))
      (node (ref "L4") (pin "1") (pinfunction "1_1") (pintype "passive"))
      (node (ref "Q7") (pin "3") (pinfunction "S_3") (pintype "passive"))
      (node (ref "Q8") (pin "2") (pinfunction "D_2") (pintype "passive"))
    )
    (net (code "116") (name "Net-(IC13-TG)") (class "Default")
      (node (ref "IC13") (pin "25") (pinfunction "TG_25") (pintype "output"))
      (node (ref "Q7") (pin "1") (pinfunction "G_1") (pintype "passive"))
    )
    (net (code "117") (name "Net-(IC13-VC)") (class "Default")
      (node (ref "C87") (pin "2") (pinfunction "2_2") (pintype "passive"))
      (node (ref "IC13") (pin "18") (pinfunction "VC_18") (pintype "passive"))
    )
    (net (code "118") (name "Net-(IC13-VIN)") (class "Default")
      (node (ref "C70") (pin "1") (pinfunction "1_1") (pintype "passive"))
      (node (ref "D10") (pin "C") (pinfunction "C_C") (pintype "passive"))
      (node (ref "D8") (pin "C") (pinfunction "C_C") (pintype "passive"))
      (node (ref "IC13") (pin "3") (pinfunction "VIN_3") (pintype "passive"))
    )
    (net (code "119") (name "Net-(IC13-~{FAULT})") (class "Default")
      (node (ref "IC13") (pin "9") (pinfunction "~{FAULT}_9") (pintype "output"))
      (node (ref "R68") (pin "1") (pinfunction "1_1") (pintype "passive"))
    )
    (net (code "120") (name "Net-(L1A-1)") (class "Default")
      (node (ref "C1") (pin "2") (pinfunction "2_2") (pintype "passive"))
      (node (ref "L1") (pin "3") (pinfunction "1_3") (pintype "passive"))
      (node (ref "R1") (pin "2") (pinfunction "2_2") (pintype "passive"))
      (node (ref "X1") (pin "1") (pinfunction "1_1") (pintype "passive"))
    )
    (net (code "121") (name "Net-(L2-Pad2)") (class "Default")
      (node (ref "L2") (pin "2") (pinfunction "2_2") (pintype "passive"))
      (node (ref "R34") (pin "1") (pinfunction "1_1") (pintype "passive"))
    )
    (net (code "122") (name "Net-(L4-Pad2)") (class "Default")
      (node (ref "L4") (pin "2") (pinfunction "2_2") (pintype "passive"))
      (node (ref "R58") (pin "1") (pinfunction "1_1") (pintype "passive"))
    )
    (net (code "123") (name "Net-(LED1-AG)") (class "Default")
      (node (ref "LED1") (pin "GREEN") (pinfunction "AG_GREEN") (pintype "passive"))
      (node (ref "Q4") (pin "2") (pinfunction "S_2") (pintype "passive"))
    )
    (net (code "124") (name "Net-(LED1-AR)") (class "Default")
      (node (ref "LED1") (pin "RED") (pinfunction "AR_RED") (pintype "passive"))
      (node (ref "R49") (pin "1") (pinfunction "1_1") (pintype "passive"))
    )
    (net (code "125") (name "Net-(LED2-AG)") (class "Default")
      (node (ref "LED2") (pin "GREEN") (pinfunction "AG_GREEN") (pintype "passive"))
      (node (ref "Q9") (pin "2") (pinfunction "S_2") (pintype "passive"))
    )
    (net (code "126") (name "Net-(LED2-AR)") (class "Default")
      (node (ref "LED2") (pin "RED") (pinfunction "AR_RED") (pintype "passive"))
      (node (ref "R73") (pin "1") (pinfunction "1_1") (pintype "passive"))
    )
    (net (code "127") (name "Net-(Q1-D-Pad2)") (class "Default")
      (node (ref "Q1") (pin "2") (pinfunction "D_2") (pintype "passive"))
      (node (ref "Q1") (pin "4") (pinfunction "D_4") (pintype "passive"))
      (node (ref "R28") (pin "2") (pinfunction "2_2") (pintype "passive"))
    )
    (net (code "128") (name "Net-(Q1-G)") (class "Default")
      (node (ref "D4") (pin "C") (pinfunction "C_C") (pintype "passive"))
      (node (ref "Q1") (pin "1") (pinfunction "G_1") (pintype "passive"))
      (node (ref "R29") (pin "2") (pinfunction "2_2") (pintype "passive"))
      (node (ref "ZD2") (pin "C") (pinfunction "C_C") (pintype "passive"))
    )
    (net (code "129") (name "Net-(Q1-S)") (class "Default")
      (node (ref "D3") (pin "A") (pinfunction "A_A") (pintype "passive"))
      (node (ref "D4") (pin "A") (pinfunction "A_A") (pintype "passive"))
      (node (ref "Q1") (pin "3") (pinfunction "S_3") (pintype "passive"))
    )
    (net (code "130") (name "Net-(Q4-D)") (class "Default")
      (node (ref "Q4") (pin "3") (pinfunction "D_3") (pintype "passive"))
      (node (ref "Q5") (pin "3") (pinfunction "D_3") (pintype "passive"))
    )
    (net (code "131") (name "Net-(Q6-D-Pad2)") (class "Default")
      (node (ref "Q6") (pin "2") (pinfunction "D_2") (pintype "passive"))
      (node (ref "Q6") (pin "4") (pinfunction "D_4") (pintype "passive"))
      (node (ref "R52") (pin "2") (pinfunction "2_2") (pintype "passive"))
    )
    (net (code "132") (name "Net-(Q6-G)") (class "Default")
      (node (ref "D9") (pin "C") (pinfunction "C_C") (pintype "passive"))
      (node (ref "Q6") (pin "1") (pinfunction "G_1") (pintype "passive"))
      (node (ref "R53") (pin "2") (pinfunction "2_2") (pintype "passive"))
      (node (ref "ZD4") (pin "C") (pinfunction "C_C") (pintype "passive"))
    )
    (net (code "133") (name "Net-(Q6-S)") (class "Default")
      (node (ref "D8") (pin "A") (pinfunction "A_A") (pintype "passive"))
      (node (ref "D9") (pin "A") (pinfunction "A_A") (pintype "passive"))
      (node (ref "Q6") (pin "3") (pinfunction "S_3") (pintype "passive"))
    )
    (net (code "134") (name "Net-(Q10-D)") (class "Default")
      (node (ref "Q10") (pin "3") (pinfunction "D_3") (pintype "passive"))
      (node (ref "Q9") (pin "3") (pinfunction "D_3") (pintype "passive"))
    )
    (net (code "135") (name "Net-(R34-Pad1S)") (class "Default")
      (node (ref "R34") (pin "1S") (pinfunction "1S_1S") (pintype "passive"))
      (node (ref "R35") (pin "2") (pinfunction "2_2") (pintype "passive"))
    )
    (net (code "136") (name "Net-(R34-Pad2S)") (class "Default")
      (node (ref "R34") (pin "2S") (pinfunction "2S_2S") (pintype "passive"))
      (node (ref "R36") (pin "2") (pinfunction "2_2") (pintype "passive"))
    )
    (net (code "137") (name "Net-(R58-Pad1S)") (class "Default")
      (node (ref "R58") (pin "1S") (pinfunction "1S_1S") (pintype "passive"))
      (node (ref "R59") (pin "2") (pinfunction "2_2") (pintype "passive"))
    )
    (net (code "138") (name "Net-(R58-Pad2S)") (class "Default")
      (node (ref "R58") (pin "2S") (pinfunction "2S_2S") (pintype "passive"))
      (node (ref "R60") (pin "2") (pinfunction "2_2") (pintype "passive"))
    )
    (net (code "139") (name "Net-(X1B-1)") (class "Default")
      (node (ref "C1") (pin "1") (pinfunction "1_1") (pintype "passive"))
      (node (ref "L1") (pin "1") (pinfunction "1_1") (pintype "passive"))
      (node (ref "R1") (pin "1") (pinfunction "1_1") (pintype "passive"))
      (node (ref "X1") (pin "2") (pinfunction "1_2") (pintype "passive"))
    )
    (net (code "140") (name "Net-(X3A-S)") (class "Default")
      (node (ref "JP2") (pin "2") (pinfunction "2_2") (pintype "passive"))
      (node (ref "R19") (pin "2") (pinfunction "2_2") (pintype "passive"))
      (node (ref "X3") (pin "1") (pinfunction "S_1") (pintype "passive"))
    )
    (net (code "141") (name "OE#1") (class "Default")
      (node (ref "IC11") (pin "4") (pinfunction "EV/UVLO_4") (pintype "input"))
      (node (ref "OE#1") (pin "2") (pinfunction "2_2") (pintype "passive"))
      (node (ref "Q4") (pin "1") (pinfunction "G_1") (pintype "passive"))
    )
    (net (code "142") (name "OE#2") (class "Default")
      (node (ref "IC13") (pin "4") (pinfunction "EV/UVLO_4") (pintype "input"))
      (node (ref "OE#2") (pin "2") (pinfunction "2_2") (pintype "passive"))
      (node (ref "Q9") (pin "1") (pinfunction "G_1") (pintype "passive"))
    )
    (net (code "143") (name "OE_SYNC") (class "Default")
      (node (ref "IC8") (pin "36") (pinfunction "PF7_36") (pintype "bidirectional"))
      (node (ref "RN1") (pin "8") (pinfunction "2_8") (pintype "passive"))
    )
    (net (code "144") (name "PE") (class "Default")
      (node (ref "C2") (pin "2") (pinfunction "2_2") (pintype "passive"))
      (node (ref "C3") (pin "1") (pinfunction "1_1") (pintype "passive"))
      (node (ref "C56") (pin "1") (pinfunction "1_1") (pintype "passive"))
      (node (ref "C63") (pin "1") (pinfunction "1_1") (pintype "passive"))
      (node (ref "C76") (pin "1") (pinfunction "1_1") (pintype "passive"))
      (node (ref "C83") (pin "1") (pinfunction "1_1") (pintype "passive"))
      (node (ref "J1") (pin "1") (pinfunction "P$1_1") (pintype "bidirectional"))
      (node (ref "J1") (pin "2") (pinfunction "P$1_2") (pintype "bidirectional"))
    )
    (net (code "145") (name "PWRGOOD") (class "Default")
      (node (ref "IC2") (pin "6") (pinfunction "PWRGD_6") (pintype "output"))
      (node (ref "IC8") (pin "40") (pinfunction "PB4_40") (pintype "bidirectional"))
    )
    (net (code "146") (name "SCLK") (class "Default")
      (node (ref "IC8") (pin "28") (pinfunction "PD8_28") (pintype "bidirectional"))
      (node (ref "RN1") (pin "7") (pinfunction "2_7") (pintype "passive"))
    )
    (net (code "147") (name "SWCLK") (class "Default")
      (node (ref "IC8") (pin "37") (pinfunction "PA14_37") (pintype "bidirectional"))
      (node (ref "RN2") (pin "2") (pinfunction "1_2") (pintype "passive"))
    )
    (net (code "148") (name "SWDIO") (class "Default")
      (node (ref "IC8") (pin "34") (pinfunction "PA13_34") (pintype "bidirectional"))
      (node (ref "RN2") (pin "4") (pinfunction "1_4") (pintype "passive"))
    )
    (net (code "149") (name "SWO") (class "Default")
      (node (ref "IC8") (pin "39") (pinfunction "PB3_39") (pintype "bidirectional"))
      (node (ref "RN2") (pin "1") (pinfunction "1_1") (pintype "passive"))
    )
    (net (code "150") (name "TCK") (class "Default")
      (node (ref "IC7") (pin "5") (pinfunction "IO4_5") (pintype "bidirectional"))
      (node (ref "RN2") (pin "7") (pinfunction "2_7") (pintype "passive"))
      (node (ref "X3") (pin "2") (pinfunction "S_2") (pintype "passive"))
    )
    (net (code "151") (name "TEMP#1") (class "Default")
      (node (ref "C34") (pin "2") (pinfunction "2_2") (pintype "passive"))
      (node (ref "IC8") (pin "10") (pinfunction "PA0_10") (pintype "bidirectional"))
      (node (ref "NTC1") (pin "2") (pinfunction "P$2_2") (pintype "bidirectional"))
      (node (ref "R21") (pin "1") (pinfunction "1_1") (pintype "passive"))
    )
    (net (code "152") (name "TEMP#2") (class "Default")
      (node (ref "C35") (pin "2") (pinfunction "2_2") (pintype "passive"))
      (node (ref "IC8") (pin "14") (pinfunction "PA4_14") (pintype "bidirectional"))
      (node (ref "NTC2") (pin "2") (pinfunction "P$2_2") (pintype "bidirectional"))
      (node (ref "R22") (pin "1") (pinfunction "1_1") (pintype "passive"))
    )
    (net (code "153") (name "TMS") (class "Default")
      (node (ref "IC7") (pin "4") (pinfunction "IO3_4") (pintype "bidirectional"))
      (node (ref "RN2") (pin "5") (pinfunction "2_5") (pintype "passive"))
      (node (ref "X3") (pin "4") (pinfunction "S_4") (pintype "passive"))
    )
    (net (code "154") (name "UART_RX") (class "Default")
      (node (ref "IC3") (pin "12") (pinfunction "B3_12") (pintype "output"))
      (node (ref "IC8") (pin "31") (pinfunction "PA10_31") (pintype "bidirectional"))
    )
    (net (code "155") (name "UART_TX") (class "Default")
      (node (ref "IC3") (pin "11") (pinfunction "B4_11") (pintype "input"))
      (node (ref "IC8") (pin "30") (pinfunction "PA9_30") (pintype "bidirectional"))
      (node (ref "TX_PU") (pin "1") (pinfunction "1_1") (pintype "passive"))
    )
    (net (code "156") (name "U_MON#1") (class "Default")
      (node (ref "C41") (pin "2") (pinfunction "2_2") (pintype "passive"))
      (node (ref "IC8") (pin "18") (pinfunction "PB0_18") (pintype "bidirectional"))
      (node (ref "R24") (pin "1") (pinfunction "1_1") (pintype "passive"))
    )
    (net (code "157") (name "U_MON#2") (class "Default")
      (node (ref "C43") (pin "2") (pinfunction "2_2") (pintype "passive"))
      (node (ref "IC8") (pin "20") (pinfunction "PB2_20") (pintype "bidirectional"))
      (node (ref "R26") (pin "1") (pinfunction "1_1") (pintype "passive"))
    )
    (net (code "158") (name "U_MON1") (class "Default")
      (node (ref "R24") (pin "2") (pinfunction "2_2") (pintype "passive"))
      (node (ref "R40") (pin "1") (pinfunction "1_1") (pintype "passive"))
      (node (ref "R47") (pin "2") (pinfunction "2_2") (pintype "passive"))
    )
    (net (code "159") (name "U_MON2") (class "Default")
      (node (ref "R26") (pin "2") (pinfunction "2_2") (pintype "passive"))
      (node (ref "R64") (pin "1") (pinfunction "1_1") (pintype "passive"))
      (node (ref "R71") (pin "2") (pinfunction "2_2") (pintype "passive"))
    )
    (net (code "160") (name "U_SET#1") (class "Default")
      (node (ref "R48") (pin "1") (pinfunction "1_1") (pintype "passive"))
      (node (ref "U_SET1") (pin "1") (pinfunction "1_1") (pintype "passive"))
    )
    (net (code "161") (name "U_SET#2") (class "Default")
      (node (ref "R72") (pin "1") (pinfunction "1_1") (pintype "passive"))
      (node (ref "U_SET2") (pin "1") (pinfunction "1_1") (pintype "passive"))
    )
    (net (code "162") (name "U_SET_OUT#1") (class "Default")
      (node (ref "IC8") (pin "16") (pinfunction "PA6_16") (pintype "bidirectional"))
      (node (ref "U_SET1") (pin "2") (pinfunction "2_2") (pintype "passive"))
    )
    (net (code "163") (name "U_SET_OUT#2") (class "Default")
      (node (ref "IC8") (pin "15") (pinfunction "PA5_15") (pintype "bidirectional"))
      (node (ref "U_SET2") (pin "2") (pinfunction "2_2") (pintype "passive"))
    )
    (net (code "164") (name "V+") (class "Default")
      (node (ref "C17") (pin "1") (pinfunction "1_1") (pintype "passive"))
      (node (ref "C20") (pin "2") (pinfunction "2_2") (pintype "passive"))
      (node (ref "C7") (pin "1") (pinfunction "1_1") (pintype "passive"))
      (node (ref "IC1") (pin "1") (pinfunction "VDD1_1") (pintype "passive"))
      (node (ref "IC3") (pin "1") (pinfunction "VDD1_1") (pintype "passive"))
      (node (ref "IC3") (pin "7") (pinfunction "EN1_7") (pintype "input"))
      (node (ref "IC4") (pin "8") (pinfunction "VCC_8") (pintype "power_in"))
      (node (ref "R11") (pin "1") (pinfunction "1_1") (pintype "passive"))
      (node (ref "R12") (pin "1") (pinfunction "1_1") (pintype "passive"))
      (node (ref "R13") (pin "1") (pinfunction "1_1") (pintype "passive"))
      (node (ref "X2") (pin "1") (pinfunction "1_1") (pintype "passive"))
    )
    (net (code "165") (name "VDDA") (class "Default")
      (node (ref "C37") (pin "2") (pinfunction "2_2") (pintype "passive"))
      (node (ref "C38") (pin "2") (pinfunction "2_2") (pintype "passive"))
      (node (ref "FB1") (pin "P$2") (pinfunction "2_P$2") (pintype "passive"))
      (node (ref "IC8") (pin "24") (pinfunction "VDDSD_24") (pintype "passive"))
    )
    (net (code "166") (name "VOUT1+") (class "Default")
      (node (ref "C59") (pin "1") (pinfunction "1_1") (pintype "passive"))
      (node (ref "C60") (pin "1") (pinfunction "1_1") (pintype "passive"))
      (node (ref "C62") (pin "+") (pinfunction "+_+") (pintype "passive"))
      (node (ref "L3") (pin "1") (pinfunction "1_1") (pintype "passive"))
      (node (ref "R34") (pin "2") (pinfunction "2_2") (pintype "passive"))
      (node (ref "R39") (pin "2") (pinfunction "2_2") (pintype "passive"))
      (node (ref "R40") (pin "2") (pinfunction "2_2") (pintype "passive"))
      (node (ref "ZD2") (pin "A") (pinfunction "A_A") (pintype "passive"))
    )
    (net (code "167") (name "VOUT2+") (class "Default")
      (node (ref "C79") (pin "1") (pinfunction "1_1") (pintype "passive"))
      (node (ref "C80") (pin "1") (pinfunction "1_1") (pintype "passive"))
      (node (ref "C82") (pin "+") (pinfunction "+_+") (pintype "passive"))
      (node (ref "L5") (pin "1") (pinfunction "1_1") (pintype "passive"))
      (node (ref "R58") (pin "2") (pinfunction "2_2") (pintype "passive"))
      (node (ref "R63") (pin "2") (pinfunction "2_2") (pintype "passive"))
      (node (ref "R64") (pin "2") (pinfunction "2_2") (pintype "passive"))
      (node (ref "ZD4") (pin "A") (pinfunction "A_A") (pintype "passive"))
    )
    (net (code "168") (name "VOUT_LC1+") (class "Default")
      (node (ref "C56") (pin "2") (pinfunction "2_2") (pintype "passive"))
      (node (ref "C57") (pin "1") (pinfunction "1_1") (pintype "passive"))
      (node (ref "C61") (pin "1") (pinfunction "+_1") (pintype "passive"))
      (node (ref "CH1") (pin "TIP") (pinfunction "TIP_TIP") (pintype "bidirectional"))
      (node (ref "J2") (pin "1") (pinfunction "1_1") (pintype "passive"))
      (node (ref "J2") (pin "1.1") (pinfunction "1_1.1") (pintype "passive"))
      (node (ref "L3") (pin "2") (pinfunction "2_2") (pintype "passive"))
      (node (ref "R41") (pin "1") (pinfunction "1_1") (pintype "passive"))
      (node (ref "ZD3") (pin "C") (pinfunction "C_C") (pintype "passive"))
    )
    (net (code "169") (name "VOUT_LC2+") (class "Default")
      (node (ref "C76") (pin "2") (pinfunction "2_2") (pintype "passive"))
      (node (ref "C77") (pin "1") (pinfunction "1_1") (pintype "passive"))
      (node (ref "C81") (pin "1") (pinfunction "+_1") (pintype "passive"))
      (node (ref "CH2") (pin "TIP") (pinfunction "TIP_TIP") (pintype "bidirectional"))
      (node (ref "J4") (pin "1") (pinfunction "1_1") (pintype "passive"))
      (node (ref "J4") (pin "1.1") (pinfunction "1_1.1") (pintype "passive"))
      (node (ref "L5") (pin "2") (pinfunction "2_2") (pintype "passive"))
      (node (ref "R65") (pin "1") (pinfunction "1_1") (pintype "passive"))
      (node (ref "ZD5") (pin "C") (pinfunction "C_C") (pintype "passive"))
    )
    (net (code "170") (name "VREF1") (class "Default")
      (node (ref "C53") (pin "1") (pinfunction "1_1") (pintype "passive"))
      (node (ref "IC11") (pin "10") (pinfunction "FBIN_10") (pintype "input"))
      (node (ref "IC11") (pin "13") (pinfunction "CTRL2_13") (pintype "input"))
      (node (ref "IC11") (pin "5") (pinfunction "VREF_5") (pintype "output"))
      (node (ref "R50") (pin "2") (pinfunction "2_2") (pintype "passive"))
    )
    (net (code "171") (name "VREF2") (class "Default")
      (node (ref "C73") (pin "1") (pinfunction "1_1") (pintype "passive"))
      (node (ref "IC13") (pin "10") (pinfunction "FBIN_10") (pintype "input"))
      (node (ref "IC13") (pin "13") (pinfunction "CTRL2_13") (pintype "input"))
      (node (ref "IC13") (pin "5") (pinfunction "VREF_5") (pintype "output"))
      (node (ref "R74") (pin "2") (pinfunction "2_2") (pintype "passive"))
    )
    (net (code "172") (name "unconnected-(IC8-PA2-Pad12)") (class "Default")
      (node (ref "IC8") (pin "12") (pinfunction "PA2_12") (pintype "bidirectional"))
    )
    (net (code "173") (name "unconnected-(IC8-PA3-Pad13)") (class "Default")
      (node (ref "IC8") (pin "13") (pinfunction "PA3_13") (pintype "bidirectional"))
    )
    (net (code "174") (name "unconnected-(IC8-PA8-Pad29)") (class "Default")
      (node (ref "IC8") (pin "29") (pinfunction "PA8_29") (pintype "bidirectional"))
    )
    (net (code "175") (name "unconnected-(IC8-PA15-Pad38)") (class "Default")
      (node (ref "IC8") (pin "38") (pinfunction "PA15_38") (pintype "bidirectional"))
    )
    (net (code "176") (name "unconnected-(IC8-PB7-Pad43)") (class "Default")
      (node (ref "IC8") (pin "43") (pinfunction "PB7_43") (pintype "bidirectional"))
    )
    (net (code "177") (name "unconnected-(IC8-PE9-Pad22)") (class "Default")
      (node (ref "IC8") (pin "22") (pinfunction "PE9_22") (pintype "bidirectional"))
    )
    (net (code "178") (name "unconnected-(IC8-PF6-Pad35)") (class "Default")
      (node (ref "IC8") (pin "35") (pinfunction "PF6_35") (pintype "bidirectional"))
    )
    (net (code "179") (name "unconnected-(IC8-VBAT-Pad1)") (class "Default")
      (node (ref "IC8") (pin "1") (pinfunction "VBAT_1") (pintype "passive"))
    )
    (net (code "180") (name "unconnected-(IC11-IVINMON-Pad8)") (class "Default")
      (node (ref "IC11") (pin "8") (pinfunction "IVINMON_8") (pintype "output"))
    )
    (net (code "181") (name "unconnected-(IC11-PWMOUT-Pad24)") (class "Default")
      (node (ref "IC11") (pin "24") (pinfunction "PWMOUT_24") (pintype "output"))
    )
    (net (code "182") (name "unconnected-(IC13-IVINMON-Pad8)") (class "Default")
      (node (ref "IC13") (pin "8") (pinfunction "IVINMON_8") (pintype "output"))
    )
    (net (code "183") (name "unconnected-(IC13-PWMOUT-Pad24)") (class "Default")
      (node (ref "IC13") (pin "24") (pinfunction "PWMOUT_24") (pintype "output"))
    )
    (net (code "184") (name "~{RESET}") (class "Default")
      (node (ref "IC1") (pin "15") (pinfunction "B1_15") (pintype "output"))
      (node (ref "JP3") (pin "1") (pinfunction "1_1") (pintype "passive"))
    )
  )
)
